# receiver_2v0.net
KiCad netlist of a schematic drawn in EAGLE
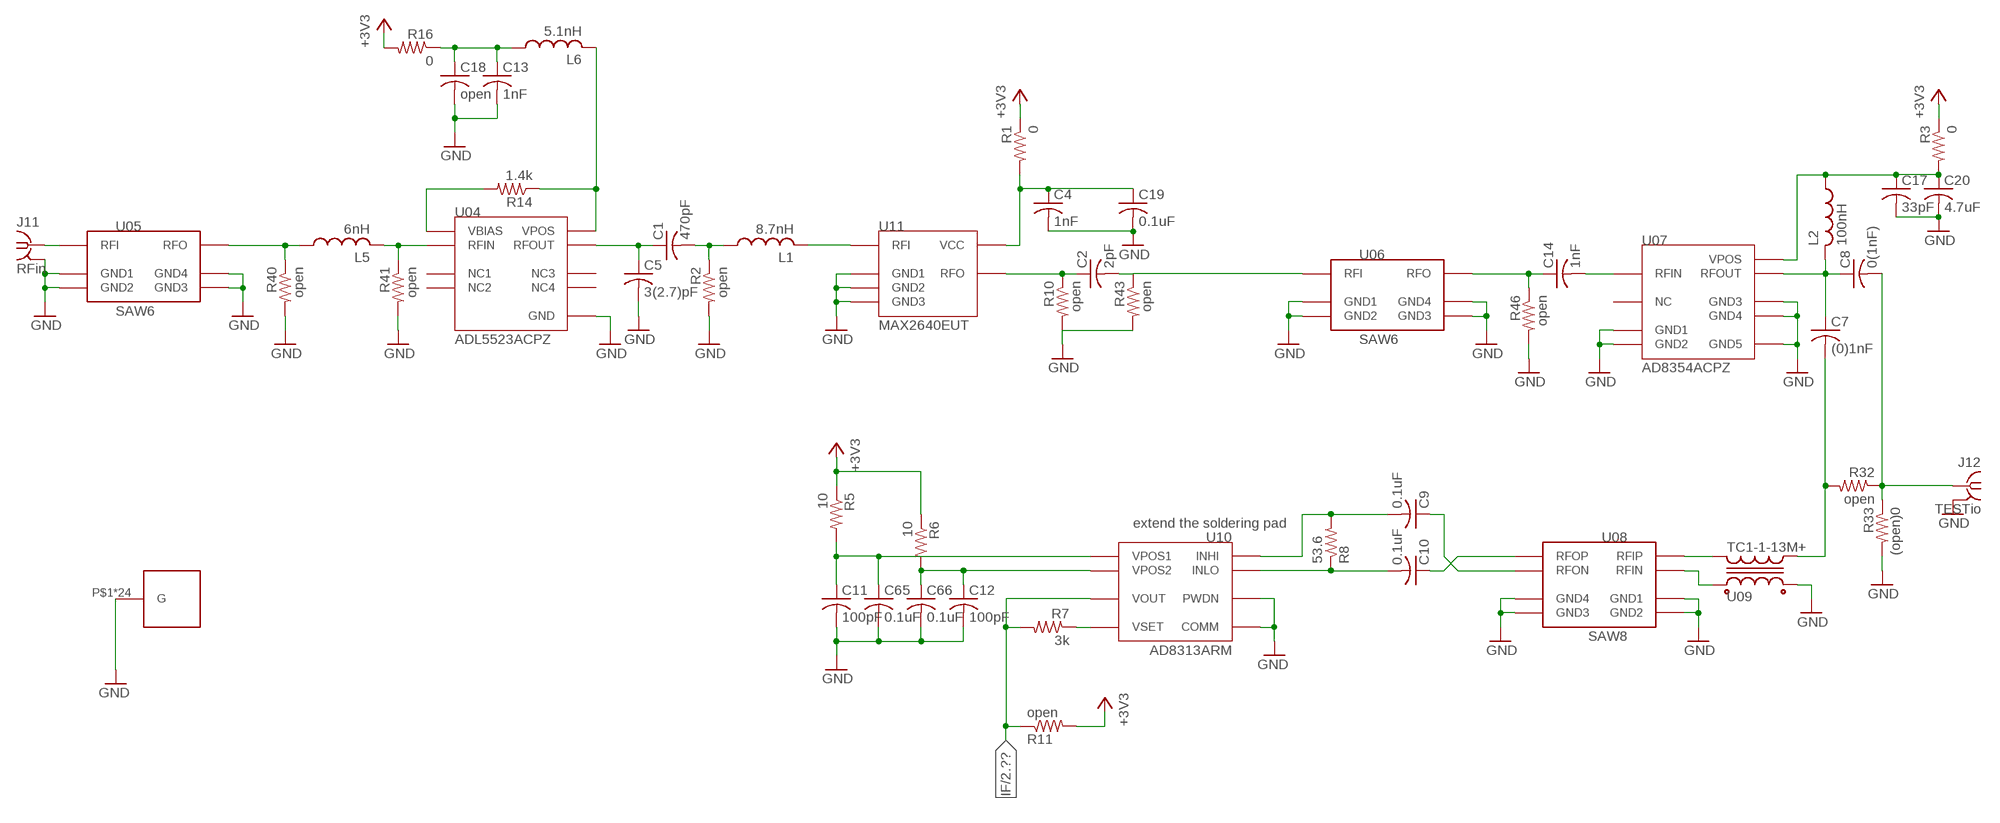
[diagram p0: schematic, sheet 1]
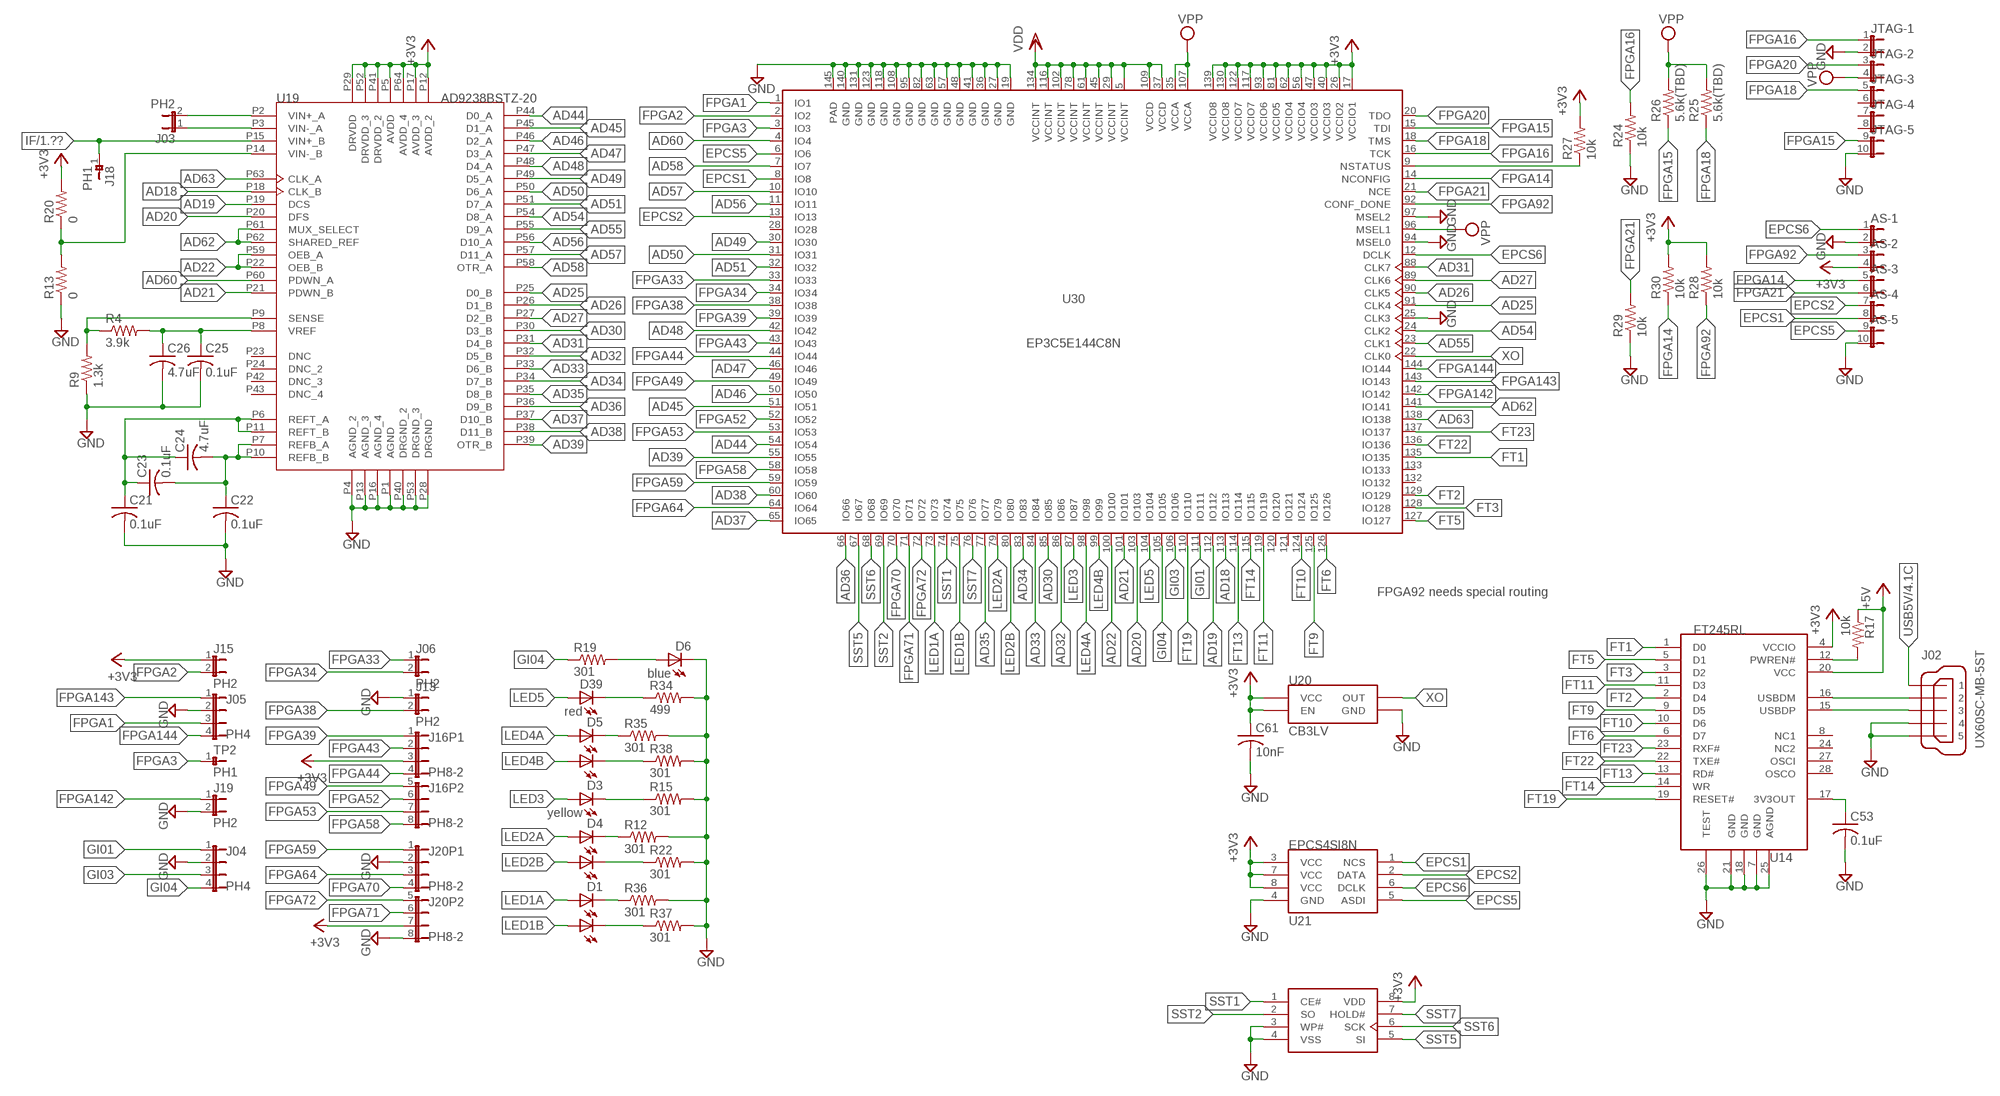
[diagram p1: schematic, sheet 2]
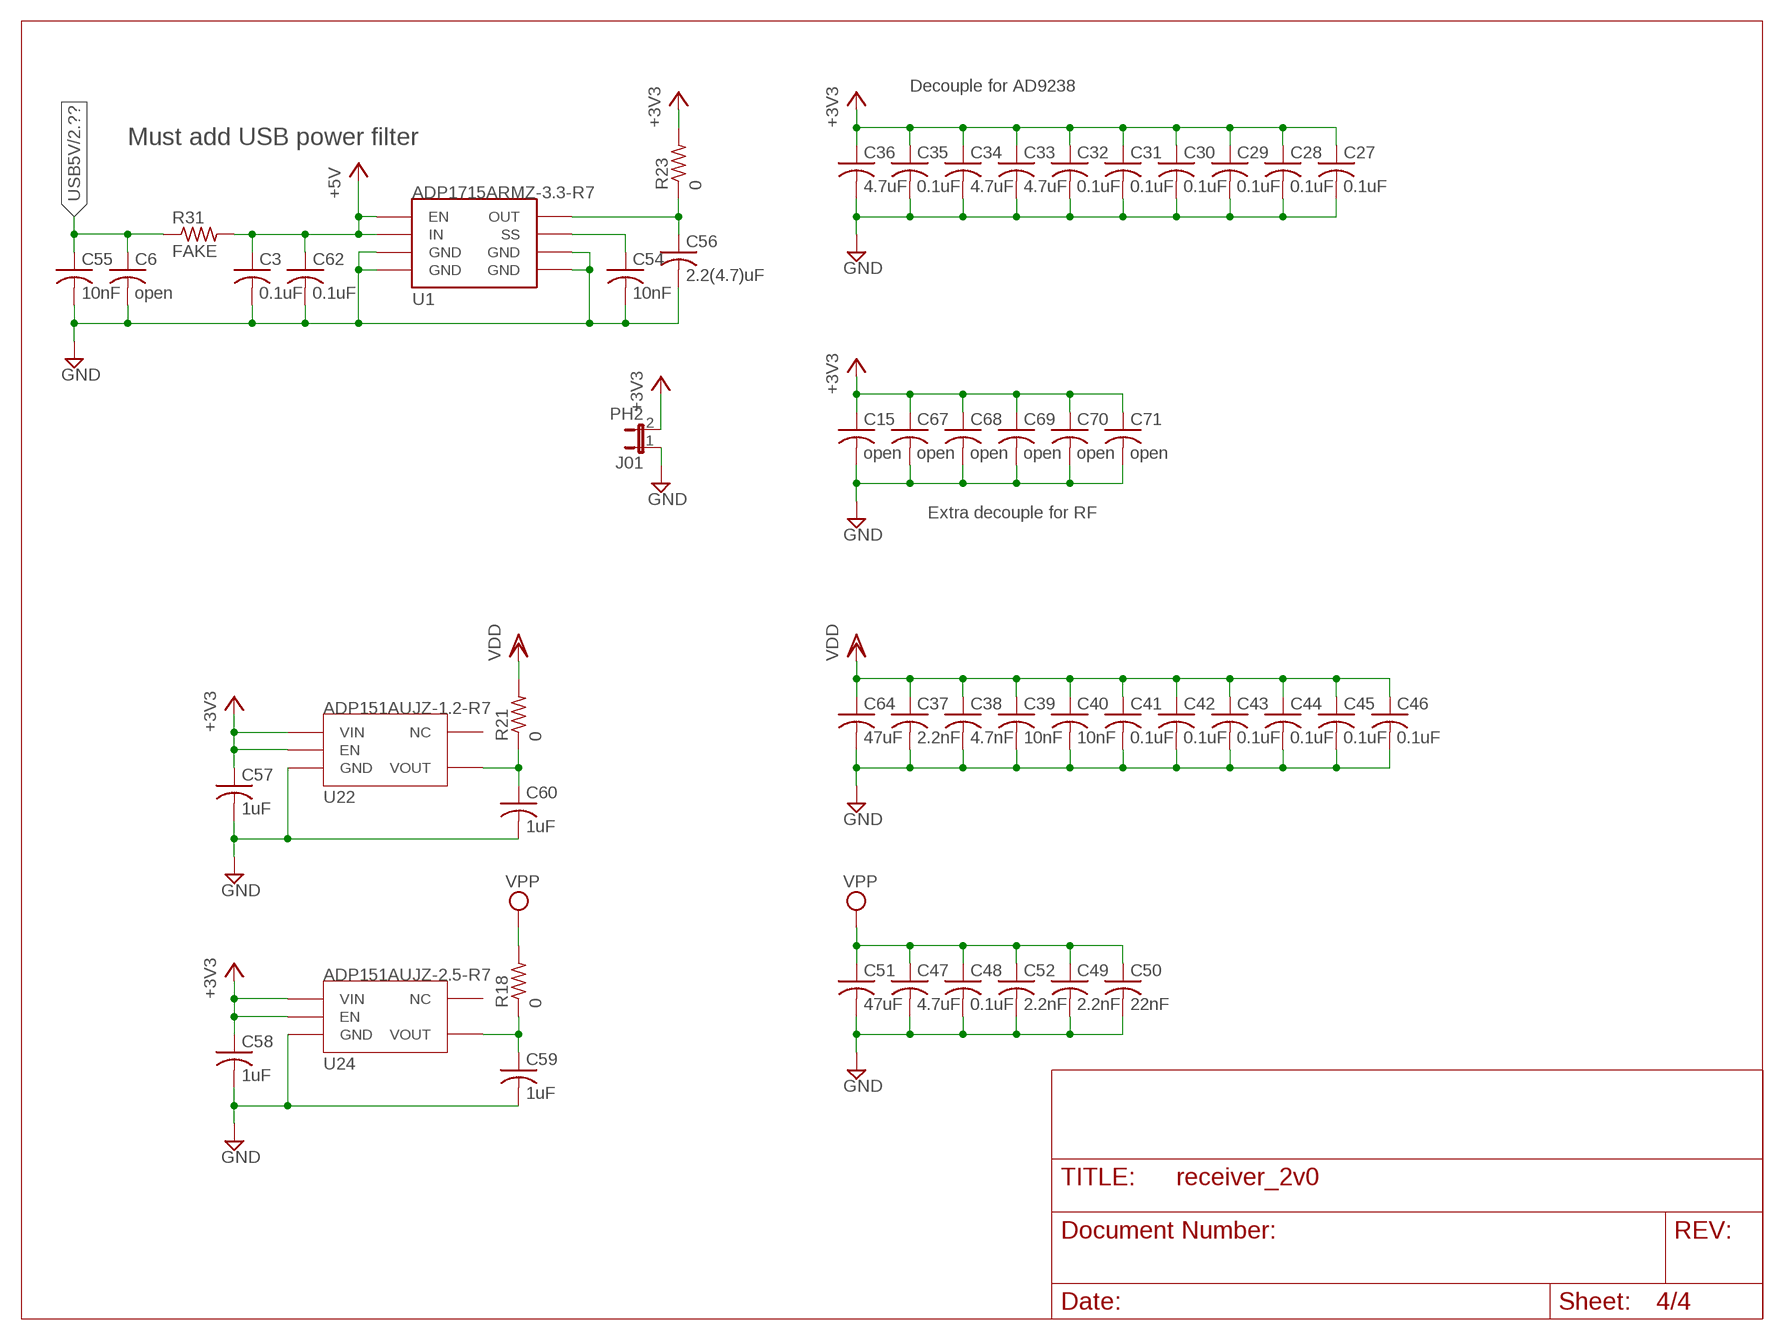
[diagram p2: schematic, sheet 4]

(export (version "E")
  (design (tool "Eeschema 10.0.6"))
  (components
    (comp (ref "C1")
      (value "470pF")
      (footprint "eagle-import:C0603")
      (libsource (lib "eagle-import") (part "C-USC0603"))
    )
    (comp (ref "C2")
      (value "2pF")
      (footprint "eagle-import:C0603")
      (libsource (lib "eagle-import") (part "C-USC0603"))
    )
    (comp (ref "C4")
      (value "1nF")
      (footprint "eagle-import:C0603")
      (libsource (lib "eagle-import") (part "C-USC0603"))
    )
    (comp (ref "C5")
      (value "3(2.7)pF")
      (footprint "eagle-import:C0603")
      (libsource (lib "eagle-import") (part "C-USC0603"))
    )
    (comp (ref "C7")
      (value "(0)1nF")
      (footprint "eagle-import:C0603")
      (libsource (lib "eagle-import") (part "C-USC0603"))
    )
    (comp (ref "C8")
      (value "0(1nF)")
      (footprint "eagle-import:C0603")
      (libsource (lib "eagle-import") (part "C-USC0603"))
    )
    (comp (ref "C9")
      (value "0.1uF")
      (footprint "eagle-import:C0603")
      (libsource (lib "eagle-import") (part "C-USC0603"))
    )
    (comp (ref "C10")
      (value "0.1uF")
      (footprint "eagle-import:C0603")
      (libsource (lib "eagle-import") (part "C-USC0603"))
    )
    (comp (ref "C11")
      (value "100pF")
      (footprint "eagle-import:C0603")
      (libsource (lib "eagle-import") (part "C-USC0603"))
    )
    (comp (ref "C12")
      (value "100pF")
      (footprint "eagle-import:C0603")
      (libsource (lib "eagle-import") (part "C-USC0603"))
    )
    (comp (ref "C13")
      (value "1nF")
      (footprint "eagle-import:C0603")
      (libsource (lib "eagle-import") (part "C-USC0603"))
    )
    (comp (ref "C14")
      (value "1nF")
      (footprint "eagle-import:C0603")
      (libsource (lib "eagle-import") (part "C-USC0603"))
    )
    (comp (ref "C17")
      (value "33pF")
      (footprint "eagle-import:C0603")
      (libsource (lib "eagle-import") (part "C-USC0603"))
    )
    (comp (ref "C18")
      (value "open")
      (footprint "eagle-import:C0603")
      (libsource (lib "eagle-import") (part "C-USC0603"))
    )
    (comp (ref "C19")
      (value "0.1uF")
      (footprint "eagle-import:C0603")
      (libsource (lib "eagle-import") (part "C-USC0603"))
    )
    (comp (ref "C20")
      (value "4.7uF")
      (footprint "eagle-import:C0603")
      (libsource (lib "eagle-import") (part "C-USC0603"))
    )
    (comp (ref "C65")
      (value "0.1uF")
      (footprint "eagle-import:C0603")
      (libsource (lib "eagle-import") (part "C-USC0603"))
    )
    (comp (ref "C66")
      (value "0.1uF")
      (footprint "eagle-import:C0603")
      (libsource (lib "eagle-import") (part "C-USC0603"))
    )
    (comp (ref "J11")
      (value "RFin")
      (footprint "eagle-import:J502-ND-142-0711-821_826")
      (fields
        (field (name "MF") "JOHNSON COMPONENTS")
        (field (name "MPN") "142-0711-821")
        (field (name "MPN_1") "142-0711-821")
        (field (name "OC_FARNELL") "1019328")
        (field (name "OC_NEWARK") "16F3627")
      )
      (libsource (lib "eagle-import") (part "SMA-142-0711-821/826"))
    )
    (comp (ref "J12")
      (value "TESTio")
      (footprint "eagle-import:J502-ND-142-0711-821_826")
      (fields
        (field (name "MF") "JOHNSON COMPONENTS")
        (field (name "MPN") "142-0711-821")
        (field (name "MPN_1") "142-0711-821")
        (field (name "OC_FARNELL") "1019328")
        (field (name "OC_NEWARK") "16F3627")
      )
      (libsource (lib "eagle-import") (part "SMA-142-0711-821/826"))
    )
    (comp (ref "L1")
      (value "8.7nH")
      (footprint "eagle-import:L0603")
      (libsource (lib "eagle-import") (part "L-USL0603"))
    )
    (comp (ref "L2")
      (value "100nH")
      (footprint "eagle-import:L0603")
      (libsource (lib "eagle-import") (part "L-USL0603"))
    )
    (comp (ref "L5")
      (value "6nH")
      (footprint "eagle-import:L0603")
      (libsource (lib "eagle-import") (part "L-USL0603"))
    )
    (comp (ref "L6")
      (value "5.1nH")
      (footprint "eagle-import:L0603")
      (libsource (lib "eagle-import") (part "L-USL0603"))
    )
    (comp (ref "R1")
      (value "0")
      (footprint "eagle-import:R0603")
      (libsource (lib "eagle-import") (part "R-US_R0603"))
    )
    (comp (ref "R2")
      (value "open")
      (footprint "eagle-import:R0603")
      (libsource (lib "eagle-import") (part "R-US_R0603"))
    )
    (comp (ref "R3")
      (value "0")
      (footprint "eagle-import:R0603")
      (libsource (lib "eagle-import") (part "R-US_R0603"))
    )
    (comp (ref "R5")
      (value "10")
      (footprint "eagle-import:R0603")
      (libsource (lib "eagle-import") (part "R-US_R0603"))
    )
    (comp (ref "R6")
      (value "10")
      (footprint "eagle-import:R0603")
      (libsource (lib "eagle-import") (part "R-US_R0603"))
    )
    (comp (ref "R7")
      (value "3k")
      (footprint "eagle-import:R0603")
      (libsource (lib "eagle-import") (part "R-US_R0603"))
    )
    (comp (ref "R8")
      (value "53.6")
      (footprint "eagle-import:R0603")
      (libsource (lib "eagle-import") (part "R-US_R0603"))
    )
    (comp (ref "R10")
      (value "open")
      (footprint "eagle-import:R0603")
      (libsource (lib "eagle-import") (part "R-US_R0603"))
    )
    (comp (ref "R11")
      (value "open")
      (footprint "eagle-import:R0603")
      (libsource (lib "eagle-import") (part "R-US_R0603"))
    )
    (comp (ref "R14")
      (value "1.4k")
      (footprint "eagle-import:R0603")
      (libsource (lib "eagle-import") (part "R-US_R0603"))
    )
    (comp (ref "R16")
      (value "0")
      (footprint "eagle-import:R0603")
      (libsource (lib "eagle-import") (part "R-US_R0603"))
    )
    (comp (ref "R32")
      (value "open")
      (footprint "eagle-import:R0603")
      (libsource (lib "eagle-import") (part "R-US_R0603"))
    )
    (comp (ref "R33")
      (value "(open)0")
      (footprint "eagle-import:R0603")
      (libsource (lib "eagle-import") (part "R-US_R0603"))
    )
    (comp (ref "R40")
      (value "open")
      (footprint "eagle-import:R0603")
      (libsource (lib "eagle-import") (part "R-US_R0603"))
    )
    (comp (ref "R41")
      (value "open")
      (footprint "eagle-import:R0603")
      (libsource (lib "eagle-import") (part "R-US_R0603"))
    )
    (comp (ref "R43")
      (value "open")
      (footprint "eagle-import:R0603")
      (libsource (lib "eagle-import") (part "R-US_R0603"))
    )
    (comp (ref "R46")
      (value "open")
      (footprint "eagle-import:R0603")
      (libsource (lib "eagle-import") (part "R-US_R0603"))
    )
    (comp (ref "U$8")
      (value "BMI-S-5")
      (footprint "eagle-import:BMI-S-105")
      (libsource (lib "eagle-import") (part "BMI-S-5"))
    )
    (comp (ref "U04")
      (value "ADL5523ACPZ")
      (footprint "eagle-import:CP-8-2")
      (libsource (lib "eagle-import") (part "ADL5523ACPZ"))
    )
    (comp (ref "U05")
      (value "SAW6")
      (footprint "eagle-import:SAW6")
      (libsource (lib "eagle-import") (part "SAW6"))
    )
    (comp (ref "U06")
      (value "SAW6")
      (footprint "eagle-import:SAW6")
      (libsource (lib "eagle-import") (part "SAW6"))
    )
    (comp (ref "U07")
      (value "AD8354ACPZ")
      (footprint "eagle-import:CP-8-1")
      (libsource (lib "eagle-import") (part "AD8354ACPZ"))
    )
    (comp (ref "U08")
      (value "SAW8")
      (footprint "eagle-import:SAW8")
      (libsource (lib "eagle-import") (part "SAW8"))
    )
    (comp (ref "U09")
      (value "TC1-1-13M+")
      (footprint "eagle-import:AT224-1A")
      (libsource (lib "eagle-import") (part "TC1-1-13M+"))
    )
    (comp (ref "U10")
      (value "AD8313ARM")
      (footprint "eagle-import:RM-08")
      (libsource (lib "eagle-import") (part "AD8313ARM"))
    )
    (comp (ref "U11")
      (value "MAX2640EUT")
      (footprint "eagle-import:SOT23-6")
      (libsource (lib "eagle-import") (part "MAX2640EUT"))
    )
    (comp (ref "C3")
      (value "0.1uF")
      (footprint "eagle-import:C0603")
      (libsource (lib "eagle-import") (part "C-USC0603"))
    )
    (comp (ref "C6")
      (value "open")
      (footprint "eagle-import:C0603")
      (libsource (lib "eagle-import") (part "C-USC0603"))
    )
    (comp (ref "C15")
      (value "open")
      (footprint "eagle-import:C0603")
      (libsource (lib "eagle-import") (part "C-USC0603"))
    )
    (comp (ref "C27")
      (value "0.1uF")
      (footprint "eagle-import:C0603")
      (libsource (lib "eagle-import") (part "C-USC0603"))
    )
    (comp (ref "C28")
      (value "0.1uF")
      (footprint "eagle-import:C0603")
      (libsource (lib "eagle-import") (part "C-USC0603"))
    )
    (comp (ref "C29")
      (value "0.1uF")
      (footprint "eagle-import:C0603")
      (libsource (lib "eagle-import") (part "C-USC0603"))
    )
    (comp (ref "C30")
      (value "0.1uF")
      (footprint "eagle-import:C0603")
      (libsource (lib "eagle-import") (part "C-USC0603"))
    )
    (comp (ref "C31")
      (value "0.1uF")
      (footprint "eagle-import:C0603")
      (libsource (lib "eagle-import") (part "C-USC0603"))
    )
    (comp (ref "C32")
      (value "0.1uF")
      (footprint "eagle-import:C0603")
      (libsource (lib "eagle-import") (part "C-USC0603"))
    )
    (comp (ref "C33")
      (value "4.7uF")
      (footprint "eagle-import:C0603")
      (libsource (lib "eagle-import") (part "C-USC0603"))
    )
    (comp (ref "C34")
      (value "4.7uF")
      (footprint "eagle-import:C0603")
      (libsource (lib "eagle-import") (part "C-USC0603"))
    )
    (comp (ref "C35")
      (value "0.1uF")
      (footprint "eagle-import:C0603")
      (libsource (lib "eagle-import") (part "C-USC0603"))
    )
    (comp (ref "C36")
      (value "4.7uF")
      (footprint "eagle-import:C0603")
      (libsource (lib "eagle-import") (part "C-USC0603"))
    )
    (comp (ref "C37")
      (value "2.2nF")
      (footprint "eagle-import:C0603")
      (libsource (lib "eagle-import") (part "C-USC0603"))
    )
    (comp (ref "C38")
      (value "4.7nF")
      (footprint "eagle-import:C0603")
      (libsource (lib "eagle-import") (part "C-USC0603"))
    )
    (comp (ref "C39")
      (value "10nF")
      (footprint "eagle-import:C0603")
      (libsource (lib "eagle-import") (part "C-USC0603"))
    )
    (comp (ref "C40")
      (value "10nF")
      (footprint "eagle-import:C0603")
      (libsource (lib "eagle-import") (part "C-USC0603"))
    )
    (comp (ref "C41")
      (value "0.1uF")
      (footprint "eagle-import:C0603")
      (libsource (lib "eagle-import") (part "C-USC0603"))
    )
    (comp (ref "C42")
      (value "0.1uF")
      (footprint "eagle-import:C0603")
      (libsource (lib "eagle-import") (part "C-USC0603"))
    )
    (comp (ref "C43")
      (value "0.1uF")
      (footprint "eagle-import:C0603")
      (libsource (lib "eagle-import") (part "C-USC0603"))
    )
    (comp (ref "C44")
      (value "0.1uF")
      (footprint "eagle-import:C0603")
      (libsource (lib "eagle-import") (part "C-USC0603"))
    )
    (comp (ref "C45")
      (value "0.1uF")
      (footprint "eagle-import:C0603")
      (libsource (lib "eagle-import") (part "C-USC0603"))
    )
    (comp (ref "C46")
      (value "0.1uF")
      (footprint "eagle-import:C0603")
      (libsource (lib "eagle-import") (part "C-USC0603"))
    )
    (comp (ref "C47")
      (value "4.7uF")
      (footprint "eagle-import:C0603")
      (libsource (lib "eagle-import") (part "C-USC0603"))
    )
    (comp (ref "C48")
      (value "0.1uF")
      (footprint "eagle-import:C0603")
      (libsource (lib "eagle-import") (part "C-USC0603"))
    )
    (comp (ref "C49")
      (value "2.2nF")
      (footprint "eagle-import:C0603")
      (libsource (lib "eagle-import") (part "C-USC0603"))
    )
    (comp (ref "C50")
      (value "22nF")
      (footprint "eagle-import:C0603")
      (libsource (lib "eagle-import") (part "C-USC0603"))
    )
    (comp (ref "C51")
      (value "47uF")
      (footprint "eagle-import:C1206")
      (libsource (lib "eagle-import") (part "C-USC1206"))
    )
    (comp (ref "C52")
      (value "2.2nF")
      (footprint "eagle-import:C0603")
      (libsource (lib "eagle-import") (part "C-USC0603"))
    )
    (comp (ref "C54")
      (value "10nF")
      (footprint "eagle-import:C0603")
      (libsource (lib "eagle-import") (part "C-USC0603"))
    )
    (comp (ref "C55")
      (value "10nF")
      (footprint "eagle-import:C0603")
      (libsource (lib "eagle-import") (part "C-USC0603"))
    )
    (comp (ref "C56")
      (value "2.2(4.7)uF")
      (footprint "eagle-import:C0603")
      (libsource (lib "eagle-import") (part "C-USC0603"))
    )
    (comp (ref "C57")
      (value "1uF")
      (footprint "eagle-import:C0603")
      (libsource (lib "eagle-import") (part "C-USC0603"))
    )
    (comp (ref "C58")
      (value "1uF")
      (footprint "eagle-import:C0603")
      (libsource (lib "eagle-import") (part "C-USC0603"))
    )
    (comp (ref "C59")
      (value "1uF")
      (footprint "eagle-import:C0603")
      (libsource (lib "eagle-import") (part "C-USC0603"))
    )
    (comp (ref "C60")
      (value "1uF")
      (footprint "eagle-import:C0603")
      (libsource (lib "eagle-import") (part "C-USC0603"))
    )
    (comp (ref "C62")
      (value "0.1uF")
      (footprint "eagle-import:C0603")
      (libsource (lib "eagle-import") (part "C-USC0603"))
    )
    (comp (ref "C64")
      (value "47uF")
      (footprint "eagle-import:C1206")
      (libsource (lib "eagle-import") (part "C-USC1206"))
    )
    (comp (ref "C67")
      (value "open")
      (footprint "eagle-import:C0603")
      (libsource (lib "eagle-import") (part "C-USC0603"))
    )
    (comp (ref "C68")
      (value "open")
      (footprint "eagle-import:C0603")
      (libsource (lib "eagle-import") (part "C-USC0603"))
    )
    (comp (ref "C69")
      (value "open")
      (footprint "eagle-import:C0603")
      (libsource (lib "eagle-import") (part "C-USC0603"))
    )
    (comp (ref "C70")
      (value "open")
      (footprint "eagle-import:C0603")
      (libsource (lib "eagle-import") (part "C-USC0603"))
    )
    (comp (ref "C71")
      (value "open")
      (footprint "eagle-import:C0603")
      (libsource (lib "eagle-import") (part "C-USC0603"))
    )
    (comp (ref "J01")
      (value "PH2")
      (footprint "eagle-import:PH2")
      (libsource (lib "eagle-import") (part "PH2"))
    )
    (comp (ref "R18")
      (value "0")
      (footprint "eagle-import:R0603")
      (libsource (lib "eagle-import") (part "R-US_R0603"))
    )
    (comp (ref "R21")
      (value "0")
      (footprint "eagle-import:R0603")
      (libsource (lib "eagle-import") (part "R-US_R0603"))
    )
    (comp (ref "R23")
      (value "0")
      (footprint "eagle-import:R0603")
      (libsource (lib "eagle-import") (part "R-US_R0603"))
    )
    (comp (ref "R31")
      (value "FAKE")
      (footprint "eagle-import:R0603")
      (libsource (lib "eagle-import") (part "R-US_R0603"))
    )
    (comp (ref "U1")
      (value "ADP1715ARMZ-3.3-R7")
      (footprint "eagle-import:RM-08")
      (libsource (lib "eagle-import") (part "ADP1715ARMZ-3.3-R7"))
    )
    (comp (ref "U22")
      (value "ADP151AUJZ-1.2-R7")
      (footprint "eagle-import:UJ-5")
      (libsource (lib "eagle-import") (part "ADP151AUJZ-1.2-R7"))
    )
    (comp (ref "U24")
      (value "ADP151AUJZ-2.5-R7")
      (footprint "eagle-import:UJ-5")
      (libsource (lib "eagle-import") (part "ADP151AUJZ-2.5-R7"))
    )
    (comp (ref "AS")
      (value "JP5QE")
      (footprint "eagle-import:JP5Q")
      (libsource (lib "eagle-import") (part "JP5QE"))
    )
    (comp (ref "C21")
      (value "0.1uF")
      (footprint "eagle-import:C0603")
      (libsource (lib "eagle-import") (part "C-USC0603"))
    )
    (comp (ref "C22")
      (value "0.1uF")
      (footprint "eagle-import:C0603")
      (libsource (lib "eagle-import") (part "C-USC0603"))
    )
    (comp (ref "C23")
      (value "0.1uF")
      (footprint "eagle-import:C0603")
      (libsource (lib "eagle-import") (part "C-USC0603"))
    )
    (comp (ref "C24")
      (value "4.7uF")
      (footprint "eagle-import:C0603")
      (libsource (lib "eagle-import") (part "C-USC0603"))
    )
    (comp (ref "C25")
      (value "0.1uF")
      (footprint "eagle-import:C0603")
      (libsource (lib "eagle-import") (part "C-USC0603"))
    )
    (comp (ref "C26")
      (value "4.7uF")
      (footprint "eagle-import:C0603")
      (libsource (lib "eagle-import") (part "C-USC0603"))
    )
    (comp (ref "C53")
      (value "0.1uF")
      (footprint "eagle-import:C0603")
      (libsource (lib "eagle-import") (part "C-USC0603"))
    )
    (comp (ref "C61")
      (value "10nF")
      (footprint "eagle-import:C0603")
      (libsource (lib "eagle-import") (part "C-USC0603"))
    )
    (comp (ref "D1")
      (value "LED0606")
      (footprint "eagle-import:LED0606")
      (libsource (lib "eagle-import") (part "LED0606"))
    )
    (comp (ref "D3")
      (value "yellow")
      (footprint "eagle-import:LED0603")
      (libsource (lib "eagle-import") (part "LED0603"))
    )
    (comp (ref "D4")
      (value "LED0606")
      (footprint "eagle-import:LED0606")
      (libsource (lib "eagle-import") (part "LED0606"))
    )
    (comp (ref "D5")
      (value "LED0606")
      (footprint "eagle-import:LED0606")
      (libsource (lib "eagle-import") (part "LED0606"))
    )
    (comp (ref "D6")
      (value "blue")
      (footprint "eagle-import:LED0603")
      (libsource (lib "eagle-import") (part "LED0603"))
    )
    (comp (ref "D39")
      (value "red")
      (footprint "eagle-import:LED0603")
      (libsource (lib "eagle-import") (part "LED0603"))
    )
    (comp (ref "J02")
      (value "UX60SC-MB-5ST")
      (footprint "eagle-import:UX60SC-MB-5ST")
      (libsource (lib "eagle-import") (part "UX60SC-MB-5ST"))
    )
    (comp (ref "J03")
      (value "PH2")
      (footprint "eagle-import:PH2")
      (libsource (lib "eagle-import") (part "PH2"))
    )
    (comp (ref "J04")
      (value "PH4")
      (footprint "eagle-import:PH4")
      (libsource (lib "eagle-import") (part "PH4"))
    )
    (comp (ref "J05")
      (value "PH4")
      (footprint "eagle-import:PH4")
      (libsource (lib "eagle-import") (part "PH4"))
    )
    (comp (ref "J06")
      (value "PH2")
      (footprint "eagle-import:PH2")
      (libsource (lib "eagle-import") (part "PH2"))
    )
    (comp (ref "J13")
      (value "PH2")
      (footprint "eagle-import:PH2")
      (libsource (lib "eagle-import") (part "PH2"))
    )
    (comp (ref "J15")
      (value "PH2")
      (footprint "eagle-import:PH2")
      (libsource (lib "eagle-import") (part "PH2"))
    )
    (comp (ref "J16")
      (value "PH8-2")
      (footprint "eagle-import:PH8-2")
      (libsource (lib "eagle-import") (part "PH8-2"))
    )
    (comp (ref "J18")
      (value "PH1")
      (footprint "eagle-import:PH1")
      (libsource (lib "eagle-import") (part "PH1"))
    )
    (comp (ref "J19")
      (value "PH2")
      (footprint "eagle-import:PH2")
      (libsource (lib "eagle-import") (part "PH2"))
    )
    (comp (ref "J20")
      (value "PH8-2")
      (footprint "eagle-import:PH8-2")
      (libsource (lib "eagle-import") (part "PH8-2"))
    )
    (comp (ref "JTAG")
      (value "JP5QE")
      (footprint "eagle-import:JP5Q")
      (libsource (lib "eagle-import") (part "JP5QE"))
    )
    (comp (ref "R4")
      (value "3.9k")
      (footprint "eagle-import:R0603")
      (libsource (lib "eagle-import") (part "R-US_R0603"))
    )
    (comp (ref "R9")
      (value "1.3k")
      (footprint "eagle-import:R0603")
      (libsource (lib "eagle-import") (part "R-US_R0603"))
    )
    (comp (ref "R12")
      (value "301")
      (footprint "eagle-import:R0603")
      (libsource (lib "eagle-import") (part "R-US_R0603"))
    )
    (comp (ref "R13")
      (value "0")
      (footprint "eagle-import:R0603")
      (libsource (lib "eagle-import") (part "R-US_R0603"))
    )
    (comp (ref "R15")
      (value "301")
      (footprint "eagle-import:R0603")
      (libsource (lib "eagle-import") (part "R-US_R0603"))
    )
    (comp (ref "R17")
      (value "10k")
      (footprint "eagle-import:R0603")
      (libsource (lib "eagle-import") (part "R-US_R0603"))
    )
    (comp (ref "R19")
      (value "301")
      (footprint "eagle-import:R0603")
      (libsource (lib "eagle-import") (part "R-US_R0603"))
    )
    (comp (ref "R20")
      (value "0")
      (footprint "eagle-import:R0603")
      (libsource (lib "eagle-import") (part "R-US_R0603"))
    )
    (comp (ref "R22")
      (value "301")
      (footprint "eagle-import:R0603")
      (libsource (lib "eagle-import") (part "R-US_R0603"))
    )
    (comp (ref "R24")
      (value "10k")
      (footprint "eagle-import:R0603")
      (libsource (lib "eagle-import") (part "R-US_R0603"))
    )
    (comp (ref "R25")
      (value "5.6k(TBD)")
      (footprint "eagle-import:R0603")
      (libsource (lib "eagle-import") (part "R-US_R0603"))
    )
    (comp (ref "R26")
      (value "5.6k(TBD)")
      (footprint "eagle-import:R0603")
      (libsource (lib "eagle-import") (part "R-US_R0603"))
    )
    (comp (ref "R27")
      (value "10k")
      (footprint "eagle-import:R0603")
      (libsource (lib "eagle-import") (part "R-US_R0603"))
    )
    (comp (ref "R28")
      (value "10k")
      (footprint "eagle-import:R0603")
      (libsource (lib "eagle-import") (part "R-US_R0603"))
    )
    (comp (ref "R29")
      (value "10k")
      (footprint "eagle-import:R0603")
      (libsource (lib "eagle-import") (part "R-US_R0603"))
    )
    (comp (ref "R30")
      (value "10k")
      (footprint "eagle-import:R0603")
      (libsource (lib "eagle-import") (part "R-US_R0603"))
    )
    (comp (ref "R34")
      (value "499")
      (footprint "eagle-import:R0603")
      (libsource (lib "eagle-import") (part "R-US_R0603"))
    )
    (comp (ref "R35")
      (value "301")
      (footprint "eagle-import:R0603")
      (libsource (lib "eagle-import") (part "R-US_R0603"))
    )
    (comp (ref "R36")
      (value "301")
      (footprint "eagle-import:R0603")
      (libsource (lib "eagle-import") (part "R-US_R0603"))
    )
    (comp (ref "R37")
      (value "301")
      (footprint "eagle-import:R0603")
      (libsource (lib "eagle-import") (part "R-US_R0603"))
    )
    (comp (ref "R38")
      (value "301")
      (footprint "eagle-import:R0603")
      (libsource (lib "eagle-import") (part "R-US_R0603"))
    )
    (comp (ref "TP2")
      (value "PH1")
      (footprint "eagle-import:PH1")
      (libsource (lib "eagle-import") (part "PH1"))
    )
    (comp (ref "U14")
      (value "FT245RL")
      (footprint "eagle-import:SSOP-28")
      (libsource (lib "eagle-import") (part "FT245RL"))
    )
    (comp (ref "U19")
      (value "AD9238BSTZ-20")
      (footprint "eagle-import:ST-64-1")
      (libsource (lib "eagle-import") (part "AD9238BSTZ-20"))
    )
    (comp (ref "U20")
      (value "CB3LV")
      (footprint "eagle-import:CB3")
      (libsource (lib "eagle-import") (part "CB3LV"))
    )
    (comp (ref "U21")
      (value "EPCS4SI8N")
      (footprint "eagle-import:SOIC-8")
      (libsource (lib "eagle-import") (part "EPCS4SI8N"))
    )
    (comp (ref "U23")
      (value "SST25VF512A-33-4C-SAE")
      (footprint "eagle-import:SOIC-8")
      (libsource (lib "eagle-import") (part "SST25VF512A-33-4C-SAE"))
    )
    (comp (ref "U30")
      (value "EP3C5E144C8N")
      (footprint "eagle-import:EQFP144")
      (libsource (lib "eagle-import") (part "EP3C5E144C8N"))
    )
  )
  (nets
    (net (code "1") (name "+3V3") (class "Default")
      (node (ref "AS") (pin "4") (pinfunction "2_4") (pintype "passive"))
      (node (ref "C15") (pin "1") (pinfunction "1_1") (pintype "passive"))
      (node (ref "C27") (pin "1") (pinfunction "1_1") (pintype "passive"))
      (node (ref "C28") (pin "1") (pinfunction "1_1") (pintype "passive"))
      (node (ref "C29") (pin "1") (pinfunction "1_1") (pintype "passive"))
      (node (ref "C30") (pin "1") (pinfunction "1_1") (pintype "passive"))
      (node (ref "C31") (pin "1") (pinfunction "1_1") (pintype "passive"))
      (node (ref "C32") (pin "1") (pinfunction "1_1") (pintype "passive"))
      (node (ref "C33") (pin "1") (pinfunction "1_1") (pintype "passive"))
      (node (ref "C34") (pin "1") (pinfunction "1_1") (pintype "passive"))
      (node (ref "C35") (pin "1") (pinfunction "1_1") (pintype "passive"))
      (node (ref "C36") (pin "1") (pinfunction "1_1") (pintype "passive"))
      (node (ref "C57") (pin "1") (pinfunction "1_1") (pintype "passive"))
      (node (ref "C58") (pin "1") (pinfunction "1_1") (pintype "passive"))
      (node (ref "C61") (pin "1") (pinfunction "1_1") (pintype "passive"))
      (node (ref "C67") (pin "1") (pinfunction "1_1") (pintype "passive"))
      (node (ref "C68") (pin "1") (pinfunction "1_1") (pintype "passive"))
      (node (ref "C69") (pin "1") (pinfunction "1_1") (pintype "passive"))
      (node (ref "C70") (pin "1") (pinfunction "1_1") (pintype "passive"))
      (node (ref "C71") (pin "1") (pinfunction "1_1") (pintype "passive"))
      (node (ref "J01") (pin "2") (pinfunction "2_2") (pintype "passive"))
      (node (ref "J15") (pin "1") (pinfunction "1_1") (pintype "passive"))
      (node (ref "J16") (pin "3") (pinfunction "3_3") (pintype "passive"))
      (node (ref "J20") (pin "7") (pinfunction "3_7") (pintype "passive"))
      (node (ref "R1") (pin "1") (pinfunction "1_1") (pintype "passive"))
      (node (ref "R11") (pin "2") (pinfunction "2_2") (pintype "passive"))
      (node (ref "R16") (pin "2") (pinfunction "2_2") (pintype "passive"))
      (node (ref "R20") (pin "2") (pinfunction "2_2") (pintype "passive"))
      (node (ref "R23") (pin "2") (pinfunction "2_2") (pintype "passive"))
      (node (ref "R27") (pin "2") (pinfunction "2_2") (pintype "passive"))
      (node (ref "R28") (pin "2") (pinfunction "2_2") (pintype "passive"))
      (node (ref "R3") (pin "1") (pinfunction "1_1") (pintype "passive"))
      (node (ref "R30") (pin "2") (pinfunction "2_2") (pintype "passive"))
      (node (ref "R5") (pin "1") (pinfunction "1_1") (pintype "passive"))
      (node (ref "R6") (pin "1") (pinfunction "1_1") (pintype "passive"))
      (node (ref "U14") (pin "4") (pinfunction "VCCIO_4") (pintype "bidirectional"))
      (node (ref "U19") (pin "P12") (pinfunction "AVDD_2_P12") (pintype "power_in"))
      (node (ref "U19") (pin "P17") (pinfunction "AVDD_3_P17") (pintype "power_in"))
      (node (ref "U19") (pin "P29") (pinfunction "DRVDD_P29") (pintype "power_in"))
      (node (ref "U19") (pin "P41") (pinfunction "DRVDD_2_P41") (pintype "power_in"))
      (node (ref "U19") (pin "P5") (pinfunction "AVDD_P5") (pintype "power_in"))
      (node (ref "U19") (pin "P52") (pinfunction "DRVDD_3_P52") (pintype "power_in"))
      (node (ref "U19") (pin "P64") (pinfunction "AVDD_4_P64") (pintype "power_in"))
      (node (ref "U20") (pin "1") (pinfunction "EN_1") (pintype "bidirectional"))
      (node (ref "U20") (pin "4") (pinfunction "VCC_4") (pintype "bidirectional"))
      (node (ref "U21") (pin "3") (pinfunction "VCC_3") (pintype "bidirectional"))
      (node (ref "U21") (pin "7") (pinfunction "VCC_7") (pintype "bidirectional"))
      (node (ref "U21") (pin "8") (pinfunction "VCC_8") (pintype "bidirectional"))
      (node (ref "U22") (pin "1") (pinfunction "VIN_1") (pintype "passive"))
      (node (ref "U22") (pin "3") (pinfunction "EN_3") (pintype "passive"))
      (node (ref "U23") (pin "8") (pinfunction "VDD_8") (pintype "bidirectional"))
      (node (ref "U24") (pin "1") (pinfunction "VIN_1") (pintype "passive"))
      (node (ref "U24") (pin "3") (pinfunction "EN_3") (pintype "passive"))
      (node (ref "U30") (pin "117") (pinfunction "VCCIO7_117") (pintype "power_in"))
      (node (ref "U30") (pin "122") (pinfunction "VCCIO7_122") (pintype "power_in"))
      (node (ref "U30") (pin "130") (pinfunction "VCCIO8_130") (pintype "power_in"))
      (node (ref "U30") (pin "139") (pinfunction "VCCIO8_139") (pintype "power_in"))
      (node (ref "U30") (pin "17") (pinfunction "VCCIO1_17") (pintype "power_in"))
      (node (ref "U30") (pin "26") (pinfunction "VCCIO2_26") (pintype "power_in"))
      (node (ref "U30") (pin "40") (pinfunction "VCCIO3_40") (pintype "power_in"))
      (node (ref "U30") (pin "47") (pinfunction "VCCIO3_47") (pintype "power_in"))
      (node (ref "U30") (pin "56") (pinfunction "VCCIO4_56") (pintype "power_in"))
      (node (ref "U30") (pin "62") (pinfunction "VCCIO4_62") (pintype "power_in"))
      (node (ref "U30") (pin "81") (pinfunction "VCCIO5_81") (pintype "power_in"))
      (node (ref "U30") (pin "93") (pinfunction "VCCIO6_93") (pintype "power_in"))
    )
    (net (code "2") (name "+5V") (class "Default")
      (node (ref "C3") (pin "1") (pinfunction "1_1") (pintype "passive"))
      (node (ref "C62") (pin "1") (pinfunction "1_1") (pintype "passive"))
      (node (ref "R17") (pin "1") (pinfunction "1_1") (pintype "passive"))
      (node (ref "R31") (pin "2") (pinfunction "2_2") (pintype "passive"))
      (node (ref "U1") (pin "1") (pinfunction "EN_1") (pintype "passive"))
      (node (ref "U1") (pin "2") (pinfunction "IN_2") (pintype "passive"))
      (node (ref "U14") (pin "20") (pinfunction "VCC_20") (pintype "bidirectional"))
    )
    (net (code "3") (name "AD18") (class "Default")
      (node (ref "U19") (pin "P18") (pinfunction "CLK_B_P18") (pintype "passive"))
      (node (ref "U30") (pin "113") (pinfunction "IO113_113") (pintype "bidirectional"))
    )
    (net (code "4") (name "AD19") (class "Default")
      (node (ref "U19") (pin "P19") (pinfunction "DCS_P19") (pintype "passive"))
      (node (ref "U30") (pin "112") (pinfunction "IO112_112") (pintype "bidirectional"))
    )
    (net (code "5") (name "AD20") (class "Default")
      (node (ref "U19") (pin "P20") (pinfunction "DFS_P20") (pintype "passive"))
      (node (ref "U30") (pin "103") (pinfunction "IO103_103") (pintype "bidirectional"))
    )
    (net (code "6") (name "AD21") (class "Default")
      (node (ref "U19") (pin "P21") (pinfunction "PDWN_B_P21") (pintype "passive"))
      (node (ref "U30") (pin "101") (pinfunction "IO101_101") (pintype "bidirectional"))
    )
    (net (code "7") (name "AD22") (class "Default")
      (node (ref "U19") (pin "P22") (pinfunction "OEB_B_P22") (pintype "passive"))
      (node (ref "U19") (pin "P59") (pinfunction "OEB_A_P59") (pintype "passive"))
      (node (ref "U30") (pin "100") (pinfunction "IO100_100") (pintype "bidirectional"))
    )
    (net (code "8") (name "AD25") (class "Default")
      (node (ref "U19") (pin "P25") (pinfunction "D0_B_P25") (pintype "passive"))
      (node (ref "U30") (pin "91") (pinfunction "CLK4_91") (pintype "passive"))
    )
    (net (code "9") (name "AD26") (class "Default")
      (node (ref "U19") (pin "P26") (pinfunction "D1_B_P26") (pintype "passive"))
      (node (ref "U30") (pin "90") (pinfunction "CLK5_90") (pintype "passive"))
    )
    (net (code "10") (name "AD27") (class "Default")
      (node (ref "U19") (pin "P27") (pinfunction "D2_B_P27") (pintype "passive"))
      (node (ref "U30") (pin "89") (pinfunction "CLK6_89") (pintype "passive"))
    )
    (net (code "11") (name "AD30") (class "Default")
      (node (ref "U19") (pin "P30") (pinfunction "D3_B_P30") (pintype "passive"))
      (node (ref "U30") (pin "85") (pinfunction "IO85_85") (pintype "bidirectional"))
    )
    (net (code "12") (name "AD31") (class "Default")
      (node (ref "U19") (pin "P31") (pinfunction "D4_B_P31") (pintype "passive"))
      (node (ref "U30") (pin "88") (pinfunction "CLK7_88") (pintype "passive"))
    )
    (net (code "13") (name "AD32") (class "Default")
      (node (ref "U19") (pin "P32") (pinfunction "D5_B_P32") (pintype "passive"))
      (node (ref "U30") (pin "86") (pinfunction "IO86_86") (pintype "bidirectional"))
    )
    (net (code "14") (name "AD33") (class "Default")
      (node (ref "U19") (pin "P33") (pinfunction "D6_B_P33") (pintype "passive"))
      (node (ref "U30") (pin "84") (pinfunction "IO84_84") (pintype "bidirectional"))
    )
    (net (code "15") (name "AD34") (class "Default")
      (node (ref "U19") (pin "P34") (pinfunction "D7_B_P34") (pintype "passive"))
      (node (ref "U30") (pin "83") (pinfunction "IO83_83") (pintype "bidirectional"))
    )
    (net (code "16") (name "AD35") (class "Default")
      (node (ref "U19") (pin "P35") (pinfunction "D8_B_P35") (pintype "passive"))
      (node (ref "U30") (pin "77") (pinfunction "IO77_77") (pintype "bidirectional"))
    )
    (net (code "17") (name "AD36") (class "Default")
      (node (ref "U19") (pin "P36") (pinfunction "D9_B_P36") (pintype "passive"))
      (node (ref "U30") (pin "66") (pinfunction "IO66_66") (pintype "bidirectional"))
    )
    (net (code "18") (name "AD37") (class "Default")
      (node (ref "U19") (pin "P37") (pinfunction "D10_B_P37") (pintype "passive"))
      (node (ref "U30") (pin "65") (pinfunction "IO65_65") (pintype "bidirectional"))
    )
    (net (code "19") (name "AD38") (class "Default")
      (node (ref "U19") (pin "P38") (pinfunction "D11_B_P38") (pintype "passive"))
      (node (ref "U30") (pin "60") (pinfunction "IO60_60") (pintype "bidirectional"))
    )
    (net (code "20") (name "AD39") (class "Default")
      (node (ref "U19") (pin "P39") (pinfunction "OTR_B_P39") (pintype "passive"))
      (node (ref "U30") (pin "55") (pinfunction "IO55_55") (pintype "bidirectional"))
    )
    (net (code "21") (name "AD44") (class "Default")
      (node (ref "U19") (pin "P44") (pinfunction "D0_A_P44") (pintype "passive"))
      (node (ref "U30") (pin "54") (pinfunction "IO54_54") (pintype "bidirectional"))
    )
    (net (code "22") (name "AD45") (class "Default")
      (node (ref "U19") (pin "P45") (pinfunction "D1_A_P45") (pintype "passive"))
      (node (ref "U30") (pin "51") (pinfunction "IO51_51") (pintype "bidirectional"))
    )
    (net (code "23") (name "AD46") (class "Default")
      (node (ref "U19") (pin "P46") (pinfunction "D2_A_P46") (pintype "passive"))
      (node (ref "U30") (pin "50") (pinfunction "IO50_50") (pintype "bidirectional"))
    )
    (net (code "24") (name "AD47") (class "Default")
      (node (ref "U19") (pin "P47") (pinfunction "D3_A_P47") (pintype "passive"))
      (node (ref "U30") (pin "46") (pinfunction "IO46_46") (pintype "bidirectional"))
    )
    (net (code "25") (name "AD48") (class "Default")
      (node (ref "U19") (pin "P48") (pinfunction "D4_A_P48") (pintype "passive"))
      (node (ref "U30") (pin "42") (pinfunction "IO42_42") (pintype "bidirectional"))
    )
    (net (code "26") (name "AD49") (class "Default")
      (node (ref "U19") (pin "P49") (pinfunction "D5_A_P49") (pintype "passive"))
      (node (ref "U30") (pin "30") (pinfunction "IO30_30") (pintype "bidirectional"))
    )
    (net (code "27") (name "AD50") (class "Default")
      (node (ref "U19") (pin "P50") (pinfunction "D6_A_P50") (pintype "passive"))
      (node (ref "U30") (pin "31") (pinfunction "IO31_31") (pintype "bidirectional"))
    )
    (net (code "28") (name "AD51") (class "Default")
      (node (ref "U19") (pin "P51") (pinfunction "D7_A_P51") (pintype "passive"))
      (node (ref "U30") (pin "32") (pinfunction "IO32_32") (pintype "bidirectional"))
    )
    (net (code "29") (name "AD54") (class "Default")
      (node (ref "U19") (pin "P54") (pinfunction "D8_A_P54") (pintype "passive"))
      (node (ref "U30") (pin "24") (pinfunction "CLK2_24") (pintype "passive"))
    )
    (net (code "30") (name "AD55") (class "Default")
      (node (ref "U19") (pin "P55") (pinfunction "D9_A_P55") (pintype "passive"))
      (node (ref "U30") (pin "23") (pinfunction "CLK1_23") (pintype "passive"))
    )
    (net (code "31") (name "AD56") (class "Default")
      (node (ref "U19") (pin "P56") (pinfunction "D10_A_P56") (pintype "passive"))
      (node (ref "U30") (pin "11") (pinfunction "IO11_11") (pintype "bidirectional"))
    )
    (net (code "32") (name "AD57") (class "Default")
      (node (ref "U19") (pin "P57") (pinfunction "D11_A_P57") (pintype "passive"))
      (node (ref "U30") (pin "10") (pinfunction "IO10_10") (pintype "bidirectional"))
    )
    (net (code "33") (name "AD58") (class "Default")
      (node (ref "U19") (pin "P58") (pinfunction "OTR_A_P58") (pintype "passive"))
      (node (ref "U30") (pin "7") (pinfunction "IO7_7") (pintype "output"))
    )
    (net (code "34") (name "AD60") (class "Default")
      (node (ref "U19") (pin "P60") (pinfunction "PDWN_A_P60") (pintype "passive"))
      (node (ref "U30") (pin "4") (pinfunction "IO4_4") (pintype "passive"))
    )
    (net (code "35") (name "AD62") (class "Default")
      (node (ref "U19") (pin "P61") (pinfunction "MUX_SELECT_P61") (pintype "passive"))
      (node (ref "U19") (pin "P62") (pinfunction "SHARED_REF_P62") (pintype "passive"))
      (node (ref "U30") (pin "141") (pinfunction "IO141_141") (pintype "bidirectional"))
    )
    (net (code "36") (name "AD63") (class "Default")
      (node (ref "U19") (pin "P63") (pinfunction "CLK_A_P63") (pintype "passive"))
      (node (ref "U30") (pin "138") (pinfunction "IO138_138") (pintype "bidirectional"))
    )
    (net (code "37") (name "EPCS1") (class "Default")
      (node (ref "AS") (pin "8") (pinfunction "2_8") (pintype "passive"))
      (node (ref "U21") (pin "1") (pinfunction "NCS_1") (pintype "bidirectional"))
      (node (ref "U30") (pin "8") (pinfunction "IO8_8") (pintype "output"))
    )
    (net (code "38") (name "EPCS2") (class "Default")
      (node (ref "AS") (pin "7") (pinfunction "1_7") (pintype "passive"))
      (node (ref "U21") (pin "2") (pinfunction "DATA_2") (pintype "bidirectional"))
      (node (ref "U30") (pin "13") (pinfunction "IO13_13") (pintype "bidirectional"))
    )
    (net (code "39") (name "EPCS5") (class "Default")
      (node (ref "AS") (pin "9") (pinfunction "1_9") (pintype "passive"))
      (node (ref "U21") (pin "5") (pinfunction "ASDI_5") (pintype "bidirectional"))
      (node (ref "U30") (pin "6") (pinfunction "IO6_6") (pintype "passive"))
    )
    (net (code "40") (name "EPCS6") (class "Default")
      (node (ref "AS") (pin "1") (pinfunction "1_1") (pintype "passive"))
      (node (ref "U21") (pin "6") (pinfunction "DCLK_6") (pintype "bidirectional"))
      (node (ref "U30") (pin "12") (pinfunction "DCLK_12") (pintype "passive"))
    )
    (net (code "41") (name "FPGA1") (class "Default")
      (node (ref "J05") (pin "3") (pinfunction "3_3") (pintype "passive"))
      (node (ref "U30") (pin "1") (pinfunction "IO1_1") (pintype "passive"))
    )
    (net (code "42") (name "FPGA2") (class "Default")
      (node (ref "J15") (pin "2") (pinfunction "2_2") (pintype "passive"))
      (node (ref "U30") (pin "2") (pinfunction "IO2_2") (pintype "passive"))
    )
    (net (code "43") (name "FPGA3") (class "Default")
      (node (ref "TP2") (pin "1") (pinfunction "1_1") (pintype "passive"))
      (node (ref "U30") (pin "3") (pinfunction "IO3_3") (pintype "passive"))
    )
    (net (code "44") (name "FPGA14") (class "Default")
      (node (ref "AS") (pin "5") (pinfunction "1_5") (pintype "passive"))
      (node (ref "R30") (pin "1") (pinfunction "1_1") (pintype "passive"))
      (node (ref "U30") (pin "14") (pinfunction "NCONFIG_14") (pintype "input"))
    )
    (net (code "45") (name "FPGA15") (class "Default")
      (node (ref "JTAG") (pin "9") (pinfunction "1_9") (pintype "passive"))
      (node (ref "R26") (pin "1") (pinfunction "1_1") (pintype "passive"))
      (node (ref "U30") (pin "15") (pinfunction "TDI_15") (pintype "input"))
    )
    (net (code "46") (name "FPGA16") (class "Default")
      (node (ref "JTAG") (pin "1") (pinfunction "1_1") (pintype "passive"))
      (node (ref "R24") (pin "2") (pinfunction "2_2") (pintype "passive"))
      (node (ref "U30") (pin "16") (pinfunction "TCK_16") (pintype "input"))
    )
    (net (code "47") (name "FPGA18") (class "Default")
      (node (ref "JTAG") (pin "5") (pinfunction "1_5") (pintype "passive"))
      (node (ref "R25") (pin "1") (pinfunction "1_1") (pintype "passive"))
      (node (ref "U30") (pin "18") (pinfunction "TMS_18") (pintype "input"))
    )
    (net (code "48") (name "FPGA20") (class "Default")
      (node (ref "JTAG") (pin "3") (pinfunction "1_3") (pintype "passive"))
      (node (ref "U30") (pin "20") (pinfunction "TDO_20") (pintype "output"))
    )
    (net (code "49") (name "FPGA21") (class "Default")
      (node (ref "AS") (pin "6") (pinfunction "2_6") (pintype "passive"))
      (node (ref "R29") (pin "2") (pinfunction "2_2") (pintype "passive"))
      (node (ref "U30") (pin "21") (pinfunction "NCE_21") (pintype "input"))
    )
    (net (code "50") (name "FPGA33") (class "Default")
      (node (ref "J06") (pin "1") (pinfunction "1_1") (pintype "passive"))
      (node (ref "U30") (pin "33") (pinfunction "IO33_33") (pintype "bidirectional"))
    )
    (net (code "51") (name "FPGA34") (class "Default")
      (node (ref "J06") (pin "2") (pinfunction "2_2") (pintype "passive"))
      (node (ref "U30") (pin "34") (pinfunction "IO34_34") (pintype "bidirectional"))
    )
    (net (code "52") (name "FPGA38") (class "Default")
      (node (ref "J13") (pin "2") (pinfunction "2_2") (pintype "passive"))
      (node (ref "U30") (pin "38") (pinfunction "IO38_38") (pintype "bidirectional"))
    )
    (net (code "53") (name "FPGA39") (class "Default")
      (node (ref "J16") (pin "1") (pinfunction "1_1") (pintype "passive"))
      (node (ref "U30") (pin "39") (pinfunction "IO39_39") (pintype "bidirectional"))
    )
    (net (code "54") (name "FPGA43") (class "Default")
      (node (ref "J16") (pin "2") (pinfunction "2_2") (pintype "passive"))
      (node (ref "U30") (pin "43") (pinfunction "IO43_43") (pintype "bidirectional"))
    )
    (net (code "55") (name "FPGA44") (class "Default")
      (node (ref "J16") (pin "4") (pinfunction "4_4") (pintype "passive"))
      (node (ref "U30") (pin "44") (pinfunction "IO44_44") (pintype "bidirectional"))
    )
    (net (code "56") (name "FPGA49") (class "Default")
      (node (ref "J16") (pin "5") (pinfunction "1_5") (pintype "passive"))
      (node (ref "U30") (pin "49") (pinfunction "IO49_49") (pintype "bidirectional"))
    )
    (net (code "57") (name "FPGA52") (class "Default")
      (node (ref "J16") (pin "6") (pinfunction "2_6") (pintype "passive"))
      (node (ref "U30") (pin "52") (pinfunction "IO52_52") (pintype "bidirectional"))
    )
    (net (code "58") (name "FPGA53") (class "Default")
      (node (ref "J16") (pin "7") (pinfunction "3_7") (pintype "passive"))
      (node (ref "U30") (pin "53") (pinfunction "IO53_53") (pintype "bidirectional"))
    )
    (net (code "59") (name "FPGA58") (class "Default")
      (node (ref "J16") (pin "8") (pinfunction "4_8") (pintype "passive"))
      (node (ref "U30") (pin "58") (pinfunction "IO58_58") (pintype "bidirectional"))
    )
    (net (code "60") (name "FPGA59") (class "Default")
      (node (ref "J20") (pin "1") (pinfunction "1_1") (pintype "passive"))
      (node (ref "U30") (pin "59") (pinfunction "IO59_59") (pintype "bidirectional"))
    )
    (net (code "61") (name "FPGA64") (class "Default")
      (node (ref "J20") (pin "3") (pinfunction "3_3") (pintype "passive"))
      (node (ref "U30") (pin "64") (pinfunction "IO64_64") (pintype "bidirectional"))
    )
    (net (code "62") (name "FPGA70") (class "Default")
      (node (ref "J20") (pin "4") (pinfunction "4_4") (pintype "passive"))
      (node (ref "U30") (pin "70") (pinfunction "IO70_70") (pintype "bidirectional"))
    )
    (net (code "63") (name "FPGA71") (class "Default")
      (node (ref "J20") (pin "6") (pinfunction "2_6") (pintype "passive"))
      (node (ref "U30") (pin "71") (pinfunction "IO71_71") (pintype "bidirectional"))
    )
    (net (code "64") (name "FPGA72") (class "Default")
      (node (ref "J20") (pin "5") (pinfunction "1_5") (pintype "passive"))
      (node (ref "U30") (pin "72") (pinfunction "IO72_72") (pintype "bidirectional"))
    )
    (net (code "65") (name "FPGA92") (class "Default")
      (node (ref "AS") (pin "3") (pinfunction "1_3") (pintype "passive"))
      (node (ref "R28") (pin "1") (pinfunction "1_1") (pintype "passive"))
      (node (ref "U30") (pin "92") (pinfunction "CONF_DONE_92") (pintype "input"))
    )
    (net (code "66") (name "FPGA142") (class "Default")
      (node (ref "J19") (pin "1") (pinfunction "1_1") (pintype "passive"))
      (node (ref "U30") (pin "142") (pinfunction "IO142_142") (pintype "bidirectional"))
    )
    (net (code "67") (name "FPGA143") (class "Default")
      (node (ref "J05") (pin "1") (pinfunction "1_1") (pintype "passive"))
      (node (ref "U30") (pin "143") (pinfunction "IO143_143") (pintype "bidirectional"))
    )
    (net (code "68") (name "FPGA144") (class "Default")
      (node (ref "J05") (pin "4") (pinfunction "4_4") (pintype "passive"))
      (node (ref "U30") (pin "144") (pinfunction "IO144_144") (pintype "bidirectional"))
    )
    (net (code "69") (name "FT1") (class "Default")
      (node (ref "U14") (pin "1") (pinfunction "D0_1") (pintype "bidirectional"))
      (node (ref "U30") (pin "135") (pinfunction "IO135_135") (pintype "bidirectional"))
    )
    (net (code "70") (name "FT2") (class "Default")
      (node (ref "U14") (pin "2") (pinfunction "D4_2") (pintype "bidirectional"))
      (node (ref "U30") (pin "129") (pinfunction "IO129_129") (pintype "bidirectional"))
    )
    (net (code "71") (name "FT3") (class "Default")
      (node (ref "U14") (pin "3") (pinfunction "D2_3") (pintype "bidirectional"))
      (node (ref "U30") (pin "128") (pinfunction "IO128_128") (pintype "bidirectional"))
    )
    (net (code "72") (name "FT5") (class "Default")
      (node (ref "U14") (pin "5") (pinfunction "D1_5") (pintype "bidirectional"))
      (node (ref "U30") (pin "127") (pinfunction "IO127_127") (pintype "bidirectional"))
    )
    (net (code "73") (name "FT6") (class "Default")
      (node (ref "U14") (pin "6") (pinfunction "D7_6") (pintype "bidirectional"))
      (node (ref "U30") (pin "126") (pinfunction "IO126_126") (pintype "bidirectional"))
    )
    (net (code "74") (name "FT9") (class "Default")
      (node (ref "U14") (pin "9") (pinfunction "D5_9") (pintype "bidirectional"))
      (node (ref "U30") (pin "125") (pinfunction "IO125_125") (pintype "bidirectional"))
    )
    (net (code "75") (name "FT10") (class "Default")
      (node (ref "U14") (pin "10") (pinfunction "D6_10") (pintype "bidirectional"))
      (node (ref "U30") (pin "124") (pinfunction "IO124_124") (pintype "bidirectional"))
    )
    (net (code "76") (name "FT11") (class "Default")
      (node (ref "U14") (pin "11") (pinfunction "D3_11") (pintype "bidirectional"))
      (node (ref "U30") (pin "119") (pinfunction "IO119_119") (pintype "bidirectional"))
    )
    (net (code "77") (name "FT13") (class "Default")
      (node (ref "U14") (pin "13") (pinfunction "RD#_13") (pintype "bidirectional"))
      (node (ref "U30") (pin "114") (pinfunction "IO114_114") (pintype "bidirectional"))
    )
    (net (code "78") (name "FT14") (class "Default")
      (node (ref "U14") (pin "14") (pinfunction "WR_14") (pintype "bidirectional"))
      (node (ref "U30") (pin "115") (pinfunction "IO115_115") (pintype "bidirectional"))
    )
    (net (code "79") (name "FT19") (class "Default")
      (node (ref "U14") (pin "19") (pinfunction "RESET#_19") (pintype "bidirectional"))
      (node (ref "U30") (pin "110") (pinfunction "IO110_110") (pintype "bidirectional"))
    )
    (net (code "80") (name "FT22") (class "Default")
      (node (ref "U14") (pin "22") (pinfunction "TXE#_22") (pintype "bidirectional"))
      (node (ref "U30") (pin "136") (pinfunction "IO136_136") (pintype "bidirectional"))
    )
    (net (code "81") (name "FT23") (class "Default")
      (node (ref "U14") (pin "23") (pinfunction "RXF#_23") (pintype "bidirectional"))
      (node (ref "U30") (pin "137") (pinfunction "IO137_137") (pintype "bidirectional"))
    )
    (net (code "82") (name "GI01") (class "Default")
      (node (ref "J04") (pin "1") (pinfunction "1_1") (pintype "passive"))
      (node (ref "U30") (pin "111") (pinfunction "IO111_111") (pintype "bidirectional"))
    )
    (net (code "83") (name "GI03") (class "Default")
      (node (ref "J04") (pin "3") (pinfunction "3_3") (pintype "passive"))
      (node (ref "U30") (pin "106") (pinfunction "IO106_106") (pintype "bidirectional"))
    )
    (net (code "84") (name "GI04") (class "Default")
      (node (ref "J04") (pin "4") (pinfunction "4_4") (pintype "passive"))
      (node (ref "R19") (pin "1") (pinfunction "1_1") (pintype "passive"))
      (node (ref "U30") (pin "105") (pinfunction "IO105_105") (pintype "bidirectional"))
    )
    (net (code "85") (name "GND") (class "Default")
      (node (ref "AS") (pin "10") (pinfunction "2_10") (pintype "passive"))
      (node (ref "AS") (pin "2") (pinfunction "2_2") (pintype "passive"))
      (node (ref "C11") (pin "2") (pinfunction "2_2") (pintype "passive"))
      (node (ref "C12") (pin "2") (pinfunction "2_2") (pintype "passive"))
      (node (ref "C13") (pin "2") (pinfunction "2_2") (pintype "passive"))
      (node (ref "C15") (pin "2") (pinfunction "2_2") (pintype "passive"))
      (node (ref "C17") (pin "2") (pinfunction "2_2") (pintype "passive"))
      (node (ref "C18") (pin "2") (pinfunction "2_2") (pintype "passive"))
      (node (ref "C19") (pin "2") (pinfunction "2_2") (pintype "passive"))
      (node (ref "C20") (pin "2") (pinfunction "2_2") (pintype "passive"))
      (node (ref "C21") (pin "2") (pinfunction "2_2") (pintype "passive"))
      (node (ref "C22") (pin "2") (pinfunction "2_2") (pintype "passive"))
      (node (ref "C25") (pin "2") (pinfunction "2_2") (pintype "passive"))
      (node (ref "C26") (pin "2") (pinfunction "2_2") (pintype "passive"))
      (node (ref "C27") (pin "2") (pinfunction "2_2") (pintype "passive"))
      (node (ref "C28") (pin "2") (pinfunction "2_2") (pintype "passive"))
      (node (ref "C29") (pin "2") (pinfunction "2_2") (pintype "passive"))
      (node (ref "C3") (pin "2") (pinfunction "2_2") (pintype "passive"))
      (node (ref "C30") (pin "2") (pinfunction "2_2") (pintype "passive"))
      (node (ref "C31") (pin "2") (pinfunction "2_2") (pintype "passive"))
      (node (ref "C32") (pin "2") (pinfunction "2_2") (pintype "passive"))
      (node (ref "C33") (pin "2") (pinfunction "2_2") (pintype "passive"))
      (node (ref "C34") (pin "2") (pinfunction "2_2") (pintype "passive"))
      (node (ref "C35") (pin "2") (pinfunction "2_2") (pintype "passive"))
      (node (ref "C36") (pin "2") (pinfunction "2_2") (pintype "passive"))
      (node (ref "C37") (pin "2") (pinfunction "2_2") (pintype "passive"))
      (node (ref "C38") (pin "2") (pinfunction "2_2") (pintype "passive"))
      (node (ref "C39") (pin "2") (pinfunction "2_2") (pintype "passive"))
      (node (ref "C4") (pin "2") (pinfunction "2_2") (pintype "passive"))
      (node (ref "C40") (pin "2") (pinfunction "2_2") (pintype "passive"))
      (node (ref "C41") (pin "2") (pinfunction "2_2") (pintype "passive"))
      (node (ref "C42") (pin "2") (pinfunction "2_2") (pintype "passive"))
      (node (ref "C43") (pin "2") (pinfunction "2_2") (pintype "passive"))
      (node (ref "C44") (pin "2") (pinfunction "2_2") (pintype "passive"))
      (node (ref "C45") (pin "2") (pinfunction "2_2") (pintype "passive"))
      (node (ref "C46") (pin "2") (pinfunction "2_2") (pintype "passive"))
      (node (ref "C47") (pin "2") (pinfunction "2_2") (pintype "passive"))
      (node (ref "C48") (pin "2") (pinfunction "2_2") (pintype "passive"))
      (node (ref "C49") (pin "2") (pinfunction "2_2") (pintype "passive"))
      (node (ref "C5") (pin "2") (pinfunction "2_2") (pintype "passive"))
      (node (ref "C50") (pin "2") (pinfunction "2_2") (pintype "passive"))
      (node (ref "C51") (pin "2") (pinfunction "2_2") (pintype "passive"))
      (node (ref "C52") (pin "2") (pinfunction "2_2") (pintype "passive"))
      (node (ref "C53") (pin "2") (pinfunction "2_2") (pintype "passive"))
      (node (ref "C54") (pin "2") (pinfunction "2_2") (pintype "passive"))
      (node (ref "C55") (pin "2") (pinfunction "2_2") (pintype "passive"))
      (node (ref "C56") (pin "2") (pinfunction "2_2") (pintype "passive"))
      (node (ref "C57") (pin "2") (pinfunction "2_2") (pintype "passive"))
      (node (ref "C58") (pin "2") (pinfunction "2_2") (pintype "passive"))
      (node (ref "C59") (pin "2") (pinfunction "2_2") (pintype "passive"))
      (node (ref "C6") (pin "2") (pinfunction "2_2") (pintype "passive"))
      (node (ref "C60") (pin "2") (pinfunction "2_2") (pintype "passive"))
      (node (ref "C61") (pin "2") (pinfunction "2_2") (pintype "passive"))
      (node (ref "C62") (pin "2") (pinfunction "2_2") (pintype "passive"))
      (node (ref "C64") (pin "2") (pinfunction "2_2") (pintype "passive"))
      (node (ref "C65") (pin "2") (pinfunction "2_2") (pintype "passive"))
      (node (ref "C66") (pin "2") (pinfunction "2_2") (pintype "passive"))
      (node (ref "C67") (pin "2") (pinfunction "2_2") (pintype "passive"))
      (node (ref "C68") (pin "2") (pinfunction "2_2") (pintype "passive"))
      (node (ref "C69") (pin "2") (pinfunction "2_2") (pintype "passive"))
      (node (ref "C70") (pin "2") (pinfunction "2_2") (pintype "passive"))
      (node (ref "C71") (pin "2") (pinfunction "2_2") (pintype "passive"))
      (node (ref "D6") (pin "C") (pinfunction "C_C") (pintype "passive"))
      (node (ref "J01") (pin "1") (pinfunction "1_1") (pintype "passive"))
      (node (ref "J02") (pin "4") (pinfunction "4_4") (pintype "input"))
      (node (ref "J02") (pin "5") (pinfunction "5_5") (pintype "input"))
      (node (ref "J04") (pin "2") (pinfunction "2_2") (pintype "passive"))
      (node (ref "J05") (pin "2") (pinfunction "2_2") (pintype "passive"))
      (node (ref "J11") (pin "G@1") (pinfunction "GND_G@1") (pintype "power_in"))
      (node (ref "J12") (pin "G@1") (pinfunction "GND_G@1") (pintype "power_in"))
      (node (ref "J13") (pin "1") (pinfunction "1_1") (pintype "passive"))
      (node (ref "J19") (pin "2") (pinfunction "2_2") (pintype "passive"))
      (node (ref "J20") (pin "2") (pinfunction "2_2") (pintype "passive"))
      (node (ref "J20") (pin "8") (pinfunction "4_8") (pintype "passive"))
      (node (ref "JTAG") (pin "10") (pinfunction "2_10") (pintype "passive"))
      (node (ref "JTAG") (pin "2") (pinfunction "2_2") (pintype "passive"))
      (node (ref "R10") (pin "2") (pinfunction "2_2") (pintype "passive"))
      (node (ref "R12") (pin "2") (pinfunction "2_2") (pintype "passive"))
      (node (ref "R13") (pin "1") (pinfunction "1_1") (pintype "passive"))
      (node (ref "R15") (pin "2") (pinfunction "2_2") (pintype "passive"))
      (node (ref "R2") (pin "2") (pinfunction "2_2") (pintype "passive"))
      (node (ref "R22") (pin "2") (pinfunction "2_2") (pintype "passive"))
      (node (ref "R24") (pin "1") (pinfunction "1_1") (pintype "passive"))
      (node (ref "R29") (pin "1") (pinfunction "1_1") (pintype "passive"))
      (node (ref "R33") (pin "2") (pinfunction "2_2") (pintype "passive"))
      (node (ref "R34") (pin "2") (pinfunction "2_2") (pintype "passive"))
      (node (ref "R35") (pin "2") (pinfunction "2_2") (pintype "passive"))
      (node (ref "R36") (pin "2") (pinfunction "2_2") (pintype "passive"))
      (node (ref "R37") (pin "2") (pinfunction "2_2") (pintype "passive"))
      (node (ref "R38") (pin "2") (pinfunction "2_2") (pintype "passive"))
      (node (ref "R40") (pin "2") (pinfunction "2_2") (pintype "passive"))
      (node (ref "R41") (pin "2") (pinfunction "2_2") (pintype "passive"))
      (node (ref "R43") (pin "2") (pinfunction "2_2") (pintype "passive"))
      (node (ref "R46") (pin "2") (pinfunction "2_2") (pintype "passive"))
      (node (ref "R9") (pin "1") (pinfunction "1_1") (pintype "passive"))
      (node (ref "U$8") (pin "P$1") (pinfunction "G_P$1") (pintype "bidirectional"))
      (node (ref "U$8") (pin "P$10") (pinfunction "G_P$10") (pintype "bidirectional"))
      (node (ref "U$8") (pin "P$11") (pinfunction "G_P$11") (pintype "bidirectional"))
      (node (ref "U$8") (pin "P$12") (pinfunction "G_P$12") (pintype "bidirectional"))
      (node (ref "U$8") (pin "P$13") (pinfunction "G_P$13") (pintype "bidirectional"))
      (node (ref "U$8") (pin "P$15") (pinfunction "G_P$15") (pintype "bidirectional"))
      (node (ref "U$8") (pin "P$16") (pinfunction "G_P$16") (pintype "bidirectional"))
      (node (ref "U$8") (pin "P$17") (pinfunction "G_P$17") (pintype "bidirectional"))
      (node (ref "U$8") (pin "P$18") (pinfunction "G_P$18") (pintype "bidirectional"))
      (node (ref "U$8") (pin "P$2") (pinfunction "G_P$2") (pintype "bidirectional"))
      (node (ref "U$8") (pin "P$20") (pinfunction "G_P$20") (pintype "bidirectional"))
      (node (ref "U$8") (pin "P$21") (pinfunction "G_P$21") (pintype "bidirectional"))
      (node (ref "U$8") (pin "P$22") (pinfunction "G_P$22") (pintype "bidirectional"))
      (node (ref "U$8") (pin "P$23") (pinfunction "G_P$23") (pintype "bidirectional"))
      (node (ref "U$8") (pin "P$24") (pinfunction "G_P$24") (pintype "bidirectional"))
      (node (ref "U$8") (pin "P$25") (pinfunction "G_P$25") (pintype "bidirectional"))
      (node (ref "U$8") (pin "P$26") (pinfunction "G_P$26") (pintype "bidirectional"))
      (node (ref "U$8") (pin "P$3") (pinfunction "G_P$3") (pintype "bidirectional"))
      (node (ref "U$8") (pin "P$4") (pinfunction "G_P$4") (pintype "bidirectional"))
      (node (ref "U$8") (pin "P$5") (pinfunction "G_P$5") (pintype "bidirectional"))
      (node (ref "U$8") (pin "P$6") (pinfunction "G_P$6") (pintype "bidirectional"))
      (node (ref "U$8") (pin "P$7") (pinfunction "G_P$7") (pintype "bidirectional"))
      (node (ref "U$8") (pin "P$8") (pinfunction "G_P$8") (pintype "bidirectional"))
      (node (ref "U$8") (pin "P$9") (pinfunction "G_P$9") (pintype "bidirectional"))
      (node (ref "U04") (pin "9") (pinfunction "GND_9") (pintype "passive"))
      (node (ref "U05") (pin "A") (pinfunction "GND1_A") (pintype "bidirectional"))
      (node (ref "U05") (pin "C") (pinfunction "GND2_C") (pintype "bidirectional"))
      (node (ref "U05") (pin "D") (pinfunction "GND3_D") (pintype "bidirectional"))
      (node (ref "U05") (pin "F") (pinfunction "GND4_F") (pintype "bidirectional"))
      (node (ref "U06") (pin "A") (pinfunction "GND1_A") (pintype "bidirectional"))
      (node (ref "U06") (pin "C") (pinfunction "GND2_C") (pintype "bidirectional"))
      (node (ref "U06") (pin "D") (pinfunction "GND3_D") (pintype "bidirectional"))
      (node (ref "U06") (pin "F") (pinfunction "GND4_F") (pintype "bidirectional"))
      (node (ref "U07") (pin "1") (pinfunction "GND1_1") (pintype "passive"))
      (node (ref "U07") (pin "4") (pinfunction "GND2_4") (pintype "passive"))
      (node (ref "U07") (pin "5") (pinfunction "GND3_5") (pintype "passive"))
      (node (ref "U07") (pin "8") (pinfunction "GND4_8") (pintype "passive"))
      (node (ref "U07") (pin "9") (pinfunction "GND5_9") (pintype "passive"))
      (node (ref "U08") (pin "P3") (pinfunction "GND1_P3") (pintype "bidirectional"))
      (node (ref "U08") (pin "P4") (pinfunction "GND2_P4") (pintype "bidirectional"))
      (node (ref "U08") (pin "P7") (pinfunction "GND3_P7") (pintype "bidirectional"))
      (node (ref "U08") (pin "P8") (pinfunction "GND4_P8") (pintype "bidirectional"))
      (node (ref "U09") (pin "1") (pinfunction "SD_1") (pintype "passive"))
      (node (ref "U1") (pin "5") (pinfunction "GND_5") (pintype "passive"))
      (node (ref "U1") (pin "6") (pinfunction "GND_6") (pintype "passive"))
      (node (ref "U1") (pin "7") (pinfunction "GND_7") (pintype "passive"))
      (node (ref "U1") (pin "8") (pinfunction "GND_8") (pintype "passive"))
      (node (ref "U10") (pin "5") (pinfunction "PWDN_5") (pintype "passive"))
      (node (ref "U10") (pin "6") (pinfunction "COMM_6") (pintype "passive"))
      (node (ref "U11") (pin "2") (pinfunction "GND1_2") (pintype "power_in"))
      (node (ref "U11") (pin "3") (pinfunction "GND2_3") (pintype "power_in"))
      (node (ref "U11") (pin "5") (pinfunction "GND3_5") (pintype "power_in"))
      (node (ref "U14") (pin "18") (pinfunction "GND_18") (pintype "bidirectional"))
      (node (ref "U14") (pin "21") (pinfunction "GND_21") (pintype "bidirectional"))
      (node (ref "U14") (pin "25") (pinfunction "AGND_25") (pintype "bidirectional"))
      (node (ref "U14") (pin "26") (pinfunction "TEST_26") (pintype "bidirectional"))
      (node (ref "U14") (pin "7") (pinfunction "GND_7") (pintype "bidirectional"))
      (node (ref "U19") (pin "P1") (pinfunction "AGND_P1") (pintype "passive"))
      (node (ref "U19") (pin "P13") (pinfunction "AGND_3_P13") (pintype "passive"))
      (node (ref "U19") (pin "P16") (pinfunction "AGND_4_P16") (pintype "passive"))
      (node (ref "U19") (pin "P28") (pinfunction "DRGND_P28") (pintype "passive"))
      (node (ref "U19") (pin "P4") (pinfunction "AGND_2_P4") (pintype "passive"))
      (node (ref "U19") (pin "P40") (pinfunction "DRGND_2_P40") (pintype "passive"))
      (node (ref "U19") (pin "P53") (pinfunction "DRGND_3_P53") (pintype "passive"))
      (node (ref "U20") (pin "2") (pinfunction "GND_2") (pintype "bidirectional"))
      (node (ref "U21") (pin "4") (pinfunction "GND_4") (pintype "bidirectional"))
      (node (ref "U22") (pin "2") (pinfunction "GND_2") (pintype "passive"))
      (node (ref "U23") (pin "3") (pinfunction "WP#_3") (pintype "bidirectional"))
      (node (ref "U23") (pin "4") (pinfunction "VSS_4") (pintype "bidirectional"))
      (node (ref "U24") (pin "2") (pinfunction "GND_2") (pintype "passive"))
      (node (ref "U30") (pin "108") (pinfunction "GND_108") (pintype "power_in"))
      (node (ref "U30") (pin "118") (pinfunction "GND_118") (pintype "power_in"))
      (node (ref "U30") (pin "123") (pinfunction "GND_123") (pintype "power_in"))
      (node (ref "U30") (pin "131") (pinfunction "GND_131") (pintype "power_in"))
      (node (ref "U30") (pin "140") (pinfunction "GND_140") (pintype "power_in"))
      (node (ref "U30") (pin "145") (pinfunction "PAD_145") (pintype "power_in"))
      (node (ref "U30") (pin "19") (pinfunction "GND_19") (pintype "power_in"))
      (node (ref "U30") (pin "25") (pinfunction "CLK3_25") (pintype "passive"))
      (node (ref "U30") (pin "27") (pinfunction "GND_27") (pintype "power_in"))
      (node (ref "U30") (pin "36") (pinfunction "GND_36") (pintype "power_in"))
      (node (ref "U30") (pin "41") (pinfunction "GND_41") (pintype "power_in"))
      (node (ref "U30") (pin "48") (pinfunction "GND_48") (pintype "power_in"))
      (node (ref "U30") (pin "57") (pinfunction "GND_57") (pintype "power_in"))
      (node (ref "U30") (pin "63") (pinfunction "GND_63") (pintype "power_in"))
      (node (ref "U30") (pin "82") (pinfunction "GND_82") (pintype "power_in"))
      (node (ref "U30") (pin "94") (pinfunction "MSEL0_94") (pintype "input"))
      (node (ref "U30") (pin "95") (pinfunction "GND_95") (pintype "power_in"))
      (node (ref "U30") (pin "97") (pinfunction "MSEL2_97") (pintype "input"))
    )
    (net (code "86") (name "IF") (class "Default")
      (node (ref "J18") (pin "1") (pinfunction "1_1") (pintype "passive"))
      (node (ref "R11") (pin "1") (pinfunction "1_1") (pintype "passive"))
      (node (ref "R7") (pin "2") (pinfunction "2_2") (pintype "passive"))
      (node (ref "U10") (pin "8") (pinfunction "VOUT_8") (pintype "passive"))
      (node (ref "U19") (pin "P15") (pinfunction "VIN+_B_P15") (pintype "passive"))
    )
    (net (code "87") (name "LED1A") (class "Default")
      (node (ref "D1") (pin "A1") (pinfunction "A1_A1") (pintype "passive"))
      (node (ref "U30") (pin "73") (pinfunction "IO73_73") (pintype "bidirectional"))
    )
    (net (code "88") (name "LED1B") (class "Default")
      (node (ref "D1") (pin "A0") (pinfunction "A0_A0") (pintype "passive"))
      (node (ref "U30") (pin "75") (pinfunction "IO75_75") (pintype "bidirectional"))
    )
    (net (code "89") (name "LED2A") (class "Default")
      (node (ref "D4") (pin "A1") (pinfunction "A1_A1") (pintype "passive"))
      (node (ref "U30") (pin "79") (pinfunction "IO79_79") (pintype "bidirectional"))
    )
    (net (code "90") (name "LED2B") (class "Default")
      (node (ref "D4") (pin "A0") (pinfunction "A0_A0") (pintype "passive"))
      (node (ref "U30") (pin "80") (pinfunction "IO80_80") (pintype "bidirectional"))
    )
    (net (code "91") (name "LED3") (class "Default")
      (node (ref "D3") (pin "A") (pinfunction "A_A") (pintype "passive"))
      (node (ref "U30") (pin "87") (pinfunction "IO87_87") (pintype "bidirectional"))
    )
    (net (code "92") (name "LED4A") (class "Default")
      (node (ref "D5") (pin "A1") (pinfunction "A1_A1") (pintype "passive"))
      (node (ref "U30") (pin "98") (pinfunction "IO98_98") (pintype "bidirectional"))
    )
    (net (code "93") (name "LED4B") (class "Default")
      (node (ref "D5") (pin "A0") (pinfunction "A0_A0") (pintype "passive"))
      (node (ref "U30") (pin "99") (pinfunction "IO99_99") (pintype "bidirectional"))
    )
    (net (code "94") (name "LED5") (class "Default")
      (node (ref "D39") (pin "A") (pinfunction "A_A") (pintype "passive"))
      (node (ref "U30") (pin "104") (pinfunction "IO104_104") (pintype "bidirectional"))
    )
    (net (code "95") (name "Net-(C1-Pad2)") (class "Default")
      (node (ref "C1") (pin "2") (pinfunction "2_2") (pintype "passive"))
      (node (ref "L1") (pin "1") (pinfunction "1_1") (pintype "passive"))
      (node (ref "R2") (pin "1") (pinfunction "1_1") (pintype "passive"))
    )
    (net (code "96") (name "Net-(C8-Pad2)") (class "Default")
      (node (ref "C8") (pin "2") (pinfunction "2_2") (pintype "passive"))
      (node (ref "J12") (pin "1") (pinfunction "1_1") (pintype "passive"))
      (node (ref "R32") (pin "1") (pinfunction "1_1") (pintype "passive"))
      (node (ref "R33") (pin "1") (pinfunction "1_1") (pintype "passive"))
    )
    (net (code "97") (name "Net-(C13-Pad1)") (class "Default")
      (node (ref "C13") (pin "1") (pinfunction "1_1") (pintype "passive"))
      (node (ref "C18") (pin "1") (pinfunction "1_1") (pintype "passive"))
      (node (ref "L6") (pin "1") (pinfunction "1_1") (pintype "passive"))
      (node (ref "R16") (pin "1") (pinfunction "1_1") (pintype "passive"))
    )
    (net (code "98") (name "Net-(D1-PadC0)") (class "Default")
      (node (ref "D1") (pin "C0") (pinfunction "C0_C0") (pintype "passive"))
      (node (ref "R37") (pin "1") (pinfunction "1_1") (pintype "passive"))
    )
    (net (code "99") (name "Net-(D1-PadC1)") (class "Default")
      (node (ref "D1") (pin "C1") (pinfunction "C1_C1") (pintype "passive"))
      (node (ref "R36") (pin "1") (pinfunction "1_1") (pintype "passive"))
    )
    (net (code "100") (name "Net-(D3-PadC)") (class "Default")
      (node (ref "D3") (pin "C") (pinfunction "C_C") (pintype "passive"))
      (node (ref "R15") (pin "1") (pinfunction "1_1") (pintype "passive"))
    )
    (net (code "101") (name "Net-(D4-PadC0)") (class "Default")
      (node (ref "D4") (pin "C0") (pinfunction "C0_C0") (pintype "passive"))
      (node (ref "R22") (pin "1") (pinfunction "1_1") (pintype "passive"))
    )
    (net (code "102") (name "Net-(D4-PadC1)") (class "Default")
      (node (ref "D4") (pin "C1") (pinfunction "C1_C1") (pintype "passive"))
      (node (ref "R12") (pin "1") (pinfunction "1_1") (pintype "passive"))
    )
    (net (code "103") (name "Net-(D5-PadC0)") (class "Default")
      (node (ref "D5") (pin "C0") (pinfunction "C0_C0") (pintype "passive"))
      (node (ref "R38") (pin "1") (pinfunction "1_1") (pintype "passive"))
    )
    (net (code "104") (name "Net-(D5-PadC1)") (class "Default")
      (node (ref "D5") (pin "C1") (pinfunction "C1_C1") (pintype "passive"))
      (node (ref "R35") (pin "1") (pinfunction "1_1") (pintype "passive"))
    )
    (net (code "105") (name "Net-(D6-PadA)") (class "Default")
      (node (ref "D6") (pin "A") (pinfunction "A_A") (pintype "passive"))
      (node (ref "R19") (pin "2") (pinfunction "2_2") (pintype "passive"))
    )
    (net (code "106") (name "Net-(D39-PadC)") (class "Default")
      (node (ref "D39") (pin "C") (pinfunction "C_C") (pintype "passive"))
      (node (ref "R34") (pin "1") (pinfunction "1_1") (pintype "passive"))
    )
    (net (code "107") (name "Net-(U1-OUT)") (class "Default")
      (node (ref "C56") (pin "1") (pinfunction "1_1") (pintype "passive"))
      (node (ref "R23") (pin "1") (pinfunction "1_1") (pintype "passive"))
      (node (ref "U1") (pin "3") (pinfunction "OUT_3") (pintype "passive"))
    )
    (net (code "108") (name "Net-(U1-SS)") (class "Default")
      (node (ref "C54") (pin "1") (pinfunction "1_1") (pintype "passive"))
      (node (ref "U1") (pin "4") (pinfunction "SS_4") (pintype "passive"))
    )
    (net (code "109") (name "Net-(U04-RFIN)") (class "Default")
      (node (ref "L5") (pin "2") (pinfunction "2_2") (pintype "passive"))
      (node (ref "R41") (pin "1") (pinfunction "1_1") (pintype "passive"))
      (node (ref "U04") (pin "2") (pinfunction "RFIN_2") (pintype "passive"))
    )
    (net (code "110") (name "Net-(U04-RFOUT)") (class "Default")
      (node (ref "C1") (pin "1") (pinfunction "1_1") (pintype "passive"))
      (node (ref "C5") (pin "1") (pinfunction "1_1") (pintype "passive"))
      (node (ref "U04") (pin "7") (pinfunction "RFOUT_7") (pintype "passive"))
    )
    (net (code "111") (name "Net-(U04-VBIAS)") (class "Default")
      (node (ref "R14") (pin "2") (pinfunction "2_2") (pintype "passive"))
      (node (ref "U04") (pin "1") (pinfunction "VBIAS_1") (pintype "passive"))
    )
    (net (code "112") (name "Net-(U04-VPOS)") (class "Default")
      (node (ref "L6") (pin "2") (pinfunction "2_2") (pintype "passive"))
      (node (ref "R14") (pin "1") (pinfunction "1_1") (pintype "passive"))
      (node (ref "U04") (pin "8") (pinfunction "VPOS_8") (pintype "power_in"))
    )
    (net (code "113") (name "Net-(U05-RFI)") (class "Default")
      (node (ref "J11") (pin "1") (pinfunction "1_1") (pintype "passive"))
      (node (ref "U05") (pin "B") (pinfunction "RFI_B") (pintype "bidirectional"))
    )
    (net (code "114") (name "Net-(U05-RFO)") (class "Default")
      (node (ref "L5") (pin "1") (pinfunction "1_1") (pintype "passive"))
      (node (ref "R40") (pin "1") (pinfunction "1_1") (pintype "passive"))
      (node (ref "U05") (pin "E") (pinfunction "RFO_E") (pintype "bidirectional"))
    )
    (net (code "115") (name "Net-(U06-RFI)") (class "Default")
      (node (ref "C2") (pin "2") (pinfunction "2_2") (pintype "passive"))
      (node (ref "R43") (pin "1") (pinfunction "1_1") (pintype "passive"))
      (node (ref "U06") (pin "B") (pinfunction "RFI_B") (pintype "bidirectional"))
    )
    (net (code "116") (name "Net-(U06-RFO)") (class "Default")
      (node (ref "C14") (pin "1") (pinfunction "1_1") (pintype "passive"))
      (node (ref "R46") (pin "1") (pinfunction "1_1") (pintype "passive"))
      (node (ref "U06") (pin "E") (pinfunction "RFO_E") (pintype "bidirectional"))
    )
    (net (code "117") (name "Net-(U07-RFIN)") (class "Default")
      (node (ref "C14") (pin "2") (pinfunction "2_2") (pintype "passive"))
      (node (ref "U07") (pin "3") (pinfunction "RFIN_3") (pintype "passive"))
    )
    (net (code "118") (name "Net-(U07-RFOUT)") (class "Default")
      (node (ref "C7") (pin "1") (pinfunction "1_1") (pintype "passive"))
      (node (ref "C8") (pin "1") (pinfunction "1_1") (pintype "passive"))
      (node (ref "L2") (pin "2") (pinfunction "2_2") (pintype "passive"))
      (node (ref "U07") (pin "7") (pinfunction "RFOUT_7") (pintype "passive"))
    )
    (net (code "119") (name "Net-(U07-VPOS)") (class "Default")
      (node (ref "C17") (pin "1") (pinfunction "1_1") (pintype "passive"))
      (node (ref "C20") (pin "1") (pinfunction "1_1") (pintype "passive"))
      (node (ref "L2") (pin "1") (pinfunction "1_1") (pintype "passive"))
      (node (ref "R3") (pin "2") (pinfunction "2_2") (pintype "passive"))
      (node (ref "U07") (pin "6") (pinfunction "VPOS_6") (pintype "power_in"))
    )
    (net (code "120") (name "Net-(U08-RFIN)") (class "Default")
      (node (ref "U08") (pin "P2") (pinfunction "RFIN_P2") (pintype "bidirectional"))
      (node (ref "U09") (pin "6") (pinfunction "PD_6") (pintype "passive"))
    )
    (net (code "121") (name "Net-(U08-RFIP)") (class "Default")
      (node (ref "U08") (pin "P1") (pinfunction "RFIP_P1") (pintype "bidirectional"))
      (node (ref "U09") (pin "4") (pinfunction "P_4") (pintype "passive"))
    )
    (net (code "122") (name "Net-(U08-RFON)") (class "Default")
      (node (ref "C9") (pin "1") (pinfunction "1_1") (pintype "passive"))
      (node (ref "U08") (pin "P6") (pinfunction "RFON_P6") (pintype "bidirectional"))
    )
    (net (code "123") (name "Net-(U08-RFOP)") (class "Default")
      (node (ref "C10") (pin "1") (pinfunction "1_1") (pintype "passive"))
      (node (ref "U08") (pin "P5") (pinfunction "RFOP_P5") (pintype "bidirectional"))
    )
    (net (code "124") (name "Net-(U09-S)") (class "Default")
      (node (ref "C7") (pin "2") (pinfunction "2_2") (pintype "passive"))
      (node (ref "R32") (pin "2") (pinfunction "2_2") (pintype "passive"))
      (node (ref "U09") (pin "3") (pinfunction "S_3") (pintype "passive"))
    )
    (net (code "125") (name "Net-(U10-INHI)") (class "Default")
      (node (ref "C9") (pin "2") (pinfunction "2_2") (pintype "passive"))
      (node (ref "R8") (pin "2") (pinfunction "2_2") (pintype "passive"))
      (node (ref "U10") (pin "2") (pinfunction "INHI_2") (pintype "passive"))
    )
    (net (code "126") (name "Net-(U10-INLO)") (class "Default")
      (node (ref "C10") (pin "2") (pinfunction "2_2") (pintype "passive"))
      (node (ref "R8") (pin "1") (pinfunction "1_1") (pintype "passive"))
      (node (ref "U10") (pin "3") (pinfunction "INLO_3") (pintype "passive"))
    )
    (net (code "127") (name "Net-(U10-VPOS1)") (class "Default")
      (node (ref "C11") (pin "1") (pinfunction "1_1") (pintype "passive"))
      (node (ref "C65") (pin "1") (pinfunction "1_1") (pintype "passive"))
      (node (ref "R5") (pin "2") (pinfunction "2_2") (pintype "passive"))
      (node (ref "U10") (pin "1") (pinfunction "VPOS1_1") (pintype "power_in"))
    )
    (net (code "128") (name "Net-(U10-VPOS2)") (class "Default")
      (node (ref "C12") (pin "1") (pinfunction "1_1") (pintype "passive"))
      (node (ref "C66") (pin "1") (pinfunction "1_1") (pintype "passive"))
      (node (ref "R6") (pin "2") (pinfunction "2_2") (pintype "passive"))
      (node (ref "U10") (pin "4") (pinfunction "VPOS2_4") (pintype "passive"))
    )
    (net (code "129") (name "Net-(U10-VSET)") (class "Default")
      (node (ref "R7") (pin "1") (pinfunction "1_1") (pintype "passive"))
      (node (ref "U10") (pin "7") (pinfunction "VSET_7") (pintype "passive"))
    )
    (net (code "130") (name "Net-(U11-RFI)") (class "Default")
      (node (ref "L1") (pin "2") (pinfunction "2_2") (pintype "passive"))
      (node (ref "U11") (pin "1") (pinfunction "RFI_1") (pintype "input"))
    )
    (net (code "131") (name "Net-(U11-RFO)") (class "Default")
      (node (ref "C2") (pin "1") (pinfunction "1_1") (pintype "passive"))
      (node (ref "R10") (pin "1") (pinfunction "1_1") (pintype "passive"))
      (node (ref "U11") (pin "4") (pinfunction "RFO_4") (pintype "output"))
    )
    (net (code "132") (name "Net-(U11-VCC)") (class "Default")
      (node (ref "C19") (pin "1") (pinfunction "1_1") (pintype "passive"))
      (node (ref "C4") (pin "1") (pinfunction "1_1") (pintype "passive"))
      (node (ref "R1") (pin "2") (pinfunction "2_2") (pintype "passive"))
      (node (ref "U11") (pin "6") (pinfunction "VCC_6") (pintype "power_in"))
    )
    (net (code "133") (name "Net-(U14-3V3OUT)") (class "Default")
      (node (ref "C53") (pin "1") (pinfunction "1_1") (pintype "passive"))
      (node (ref "U14") (pin "17") (pinfunction "3V3OUT_17") (pintype "bidirectional"))
    )
    (net (code "134") (name "Net-(U14-PWREN#)") (class "Default")
      (node (ref "R17") (pin "2") (pinfunction "2_2") (pintype "passive"))
      (node (ref "U14") (pin "12") (pinfunction "PWREN#_12") (pintype "bidirectional"))
    )
    (net (code "135") (name "Net-(U14-USBDM)") (class "Default")
      (node (ref "J02") (pin "2") (pinfunction "2_2") (pintype "input"))
      (node (ref "U14") (pin "16") (pinfunction "USBDM_16") (pintype "bidirectional"))
    )
    (net (code "136") (name "Net-(U14-USBDP)") (class "Default")
      (node (ref "J02") (pin "3") (pinfunction "3_3") (pintype "input"))
      (node (ref "U14") (pin "15") (pinfunction "USBDP_15") (pintype "bidirectional"))
    )
    (net (code "137") (name "Net-(U19-REFB_A)") (class "Default")
      (node (ref "C22") (pin "1") (pinfunction "1_1") (pintype "passive"))
      (node (ref "C23") (pin "2") (pinfunction "2_2") (pintype "passive"))
      (node (ref "C24") (pin "2") (pinfunction "2_2") (pintype "passive"))
      (node (ref "U19") (pin "P10") (pinfunction "REFB_B_P10") (pintype "passive"))
      (node (ref "U19") (pin "P7") (pinfunction "REFB_A_P7") (pintype "passive"))
    )
    (net (code "138") (name "Net-(U19-REFT_A)") (class "Default")
      (node (ref "C21") (pin "1") (pinfunction "1_1") (pintype "passive"))
      (node (ref "C23") (pin "1") (pinfunction "1_1") (pintype "passive"))
      (node (ref "C24") (pin "1") (pinfunction "1_1") (pintype "passive"))
      (node (ref "U19") (pin "P11") (pinfunction "REFT_B_P11") (pintype "passive"))
      (node (ref "U19") (pin "P6") (pinfunction "REFT_A_P6") (pintype "passive"))
    )
    (net (code "139") (name "Net-(U19-SENSE)") (class "Default")
      (node (ref "R4") (pin "1") (pinfunction "1_1") (pintype "passive"))
      (node (ref "R9") (pin "2") (pinfunction "2_2") (pintype "passive"))
      (node (ref "U19") (pin "P9") (pinfunction "SENSE_P9") (pintype "passive"))
    )
    (net (code "140") (name "Net-(U19-VIN+_A)") (class "Default")
      (node (ref "J03") (pin "2") (pinfunction "2_2") (pintype "passive"))
      (node (ref "U19") (pin "P2") (pinfunction "VIN+_A_P2") (pintype "passive"))
    )
    (net (code "141") (name "Net-(U19-VIN-_A)") (class "Default")
      (node (ref "J03") (pin "1") (pinfunction "1_1") (pintype "passive"))
      (node (ref "U19") (pin "P3") (pinfunction "VIN-_A_P3") (pintype "passive"))
    )
    (net (code "142") (name "Net-(U19-VIN-_B)") (class "Default")
      (node (ref "R13") (pin "2") (pinfunction "2_2") (pintype "passive"))
      (node (ref "R20") (pin "1") (pinfunction "1_1") (pintype "passive"))
      (node (ref "U19") (pin "P14") (pinfunction "VIN-_B_P14") (pintype "passive"))
    )
    (net (code "143") (name "Net-(U19-VREF)") (class "Default")
      (node (ref "C25") (pin "1") (pinfunction "1_1") (pintype "passive"))
      (node (ref "C26") (pin "1") (pinfunction "1_1") (pintype "passive"))
      (node (ref "R4") (pin "2") (pinfunction "2_2") (pintype "passive"))
      (node (ref "U19") (pin "P8") (pinfunction "VREF_P8") (pintype "passive"))
    )
    (net (code "144") (name "Net-(U22-VOUT)") (class "Default")
      (node (ref "C60") (pin "1") (pinfunction "1_1") (pintype "passive"))
      (node (ref "R21") (pin "1") (pinfunction "1_1") (pintype "passive"))
      (node (ref "U22") (pin "5") (pinfunction "VOUT_5") (pintype "passive"))
    )
    (net (code "145") (name "Net-(U24-VOUT)") (class "Default")
      (node (ref "C59") (pin "1") (pinfunction "1_1") (pintype "passive"))
      (node (ref "R18") (pin "1") (pinfunction "1_1") (pintype "passive"))
      (node (ref "U24") (pin "5") (pinfunction "VOUT_5") (pintype "passive"))
    )
    (net (code "146") (name "Net-(U30-NSTATUS)") (class "Default")
      (node (ref "R27") (pin "1") (pinfunction "1_1") (pintype "passive"))
      (node (ref "U30") (pin "9") (pinfunction "NSTATUS_9") (pintype "input"))
    )
    (net (code "147") (name "SST1") (class "Default")
      (node (ref "U23") (pin "1") (pinfunction "CE#_1") (pintype "bidirectional"))
      (node (ref "U30") (pin "74") (pinfunction "IO74_74") (pintype "bidirectional"))
    )
    (net (code "148") (name "SST2") (class "Default")
      (node (ref "U23") (pin "2") (pinfunction "SO_2") (pintype "bidirectional"))
      (node (ref "U30") (pin "69") (pinfunction "IO69_69") (pintype "bidirectional"))
    )
    (net (code "149") (name "SST5") (class "Default")
      (node (ref "U23") (pin "5") (pinfunction "SI_5") (pintype "bidirectional"))
      (node (ref "U30") (pin "67") (pinfunction "IO67_67") (pintype "bidirectional"))
    )
    (net (code "150") (name "SST6") (class "Default")
      (node (ref "U23") (pin "6") (pinfunction "SCK_6") (pintype "bidirectional"))
      (node (ref "U30") (pin "68") (pinfunction "IO68_68") (pintype "bidirectional"))
    )
    (net (code "151") (name "SST7") (class "Default")
      (node (ref "U23") (pin "7") (pinfunction "HOLD#_7") (pintype "bidirectional"))
      (node (ref "U30") (pin "76") (pinfunction "IO76_76") (pintype "bidirectional"))
    )
    (net (code "152") (name "USB5V") (class "Default")
      (node (ref "C55") (pin "1") (pinfunction "1_1") (pintype "passive"))
      (node (ref "C6") (pin "1") (pinfunction "1_1") (pintype "passive"))
      (node (ref "J02") (pin "1") (pinfunction "1_1") (pintype "input"))
      (node (ref "R31") (pin "1") (pinfunction "1_1") (pintype "passive"))
    )
    (net (code "153") (name "VDD") (class "Default")
      (node (ref "C37") (pin "1") (pinfunction "1_1") (pintype "passive"))
      (node (ref "C38") (pin "1") (pinfunction "1_1") (pintype "passive"))
      (node (ref "C39") (pin "1") (pinfunction "1_1") (pintype "passive"))
      (node (ref "C40") (pin "1") (pinfunction "1_1") (pintype "passive"))
      (node (ref "C41") (pin "1") (pinfunction "1_1") (pintype "passive"))
      (node (ref "C42") (pin "1") (pinfunction "1_1") (pintype "passive"))
      (node (ref "C43") (pin "1") (pinfunction "1_1") (pintype "passive"))
      (node (ref "C44") (pin "1") (pinfunction "1_1") (pintype "passive"))
      (node (ref "C45") (pin "1") (pinfunction "1_1") (pintype "passive"))
      (node (ref "C46") (pin "1") (pinfunction "1_1") (pintype "passive"))
      (node (ref "C64") (pin "1") (pinfunction "1_1") (pintype "passive"))
      (node (ref "R21") (pin "2") (pinfunction "2_2") (pintype "passive"))
      (node (ref "U30") (pin "102") (pinfunction "VCCINT_102") (pintype "power_in"))
      (node (ref "U30") (pin "109") (pinfunction "VCCD_109") (pintype "power_in"))
      (node (ref "U30") (pin "116") (pinfunction "VCCINT_116") (pintype "power_in"))
      (node (ref "U30") (pin "134") (pinfunction "VCCINT_134") (pintype "power_in"))
      (node (ref "U30") (pin "29") (pinfunction "VCCINT_29") (pintype "power_in"))
      (node (ref "U30") (pin "37") (pinfunction "VCCD_37") (pintype "power_in"))
      (node (ref "U30") (pin "45") (pinfunction "VCCINT_45") (pintype "power_in"))
      (node (ref "U30") (pin "5") (pinfunction "VCCINT_5") (pintype "power_in"))
      (node (ref "U30") (pin "61") (pinfunction "VCCINT_61") (pintype "power_in"))
      (node (ref "U30") (pin "78") (pinfunction "VCCINT_78") (pintype "power_in"))
    )
    (net (code "154") (name "VPP") (class "Default")
      (node (ref "C47") (pin "1") (pinfunction "1_1") (pintype "passive"))
      (node (ref "C48") (pin "1") (pinfunction "1_1") (pintype "passive"))
      (node (ref "C49") (pin "1") (pinfunction "1_1") (pintype "passive"))
      (node (ref "C50") (pin "1") (pinfunction "1_1") (pintype "passive"))
      (node (ref "C51") (pin "1") (pinfunction "1_1") (pintype "passive"))
      (node (ref "C52") (pin "1") (pinfunction "1_1") (pintype "passive"))
      (node (ref "JTAG") (pin "4") (pinfunction "2_4") (pintype "passive"))
      (node (ref "R18") (pin "2") (pinfunction "2_2") (pintype "passive"))
      (node (ref "R25") (pin "2") (pinfunction "2_2") (pintype "passive"))
      (node (ref "R26") (pin "2") (pinfunction "2_2") (pintype "passive"))
      (node (ref "U30") (pin "107") (pinfunction "VCCA_107") (pintype "power_in"))
      (node (ref "U30") (pin "35") (pinfunction "VCCA_35") (pintype "power_in"))
      (node (ref "U30") (pin "96") (pinfunction "MSEL1_96") (pintype "input"))
    )
    (net (code "155") (name "XO") (class "Default")
      (node (ref "U20") (pin "3") (pinfunction "OUT_3") (pintype "bidirectional"))
      (node (ref "U30") (pin "22") (pinfunction "CLK0_22") (pintype "passive"))
    )
    (net (code "156") (name "unconnected-(JTAGC-2-Pad6)") (class "Default")
      (node (ref "JTAG") (pin "6") (pinfunction "2_6") (pintype "passive"))
    )
    (net (code "157") (name "unconnected-(JTAGD-1-Pad7)") (class "Default")
      (node (ref "JTAG") (pin "7") (pinfunction "1_7") (pintype "passive"))
    )
    (net (code "158") (name "unconnected-(JTAGD-2-Pad8)") (class "Default")
      (node (ref "JTAG") (pin "8") (pinfunction "2_8") (pintype "passive"))
    )
    (net (code "159") (name "unconnected-(U04-NC1-Pad3)") (class "Default")
      (node (ref "U04") (pin "3") (pinfunction "NC1_3") (pintype "passive"))
    )
    (net (code "160") (name "unconnected-(U04-NC2-Pad4)") (class "Default")
      (node (ref "U04") (pin "4") (pinfunction "NC2_4") (pintype "passive"))
    )
    (net (code "161") (name "unconnected-(U04-NC3-Pad5)") (class "Default")
      (node (ref "U04") (pin "5") (pinfunction "NC3_5") (pintype "passive"))
    )
    (net (code "162") (name "unconnected-(U04-NC4-Pad6)") (class "Default")
      (node (ref "U04") (pin "6") (pinfunction "NC4_6") (pintype "passive"))
    )
    (net (code "163") (name "unconnected-(U07-NC-Pad2)") (class "Default")
      (node (ref "U07") (pin "2") (pinfunction "NC_2") (pintype "passive"))
    )
    (net (code "164") (name "unconnected-(U14-NC1-Pad8)") (class "Default")
      (node (ref "U14") (pin "8") (pinfunction "NC1_8") (pintype "bidirectional"))
    )
    (net (code "165") (name "unconnected-(U14-NC2-Pad24)") (class "Default")
      (node (ref "U14") (pin "24") (pinfunction "NC2_24") (pintype "bidirectional"))
    )
    (net (code "166") (name "unconnected-(U14-OSCI-Pad27)") (class "Default")
      (node (ref "U14") (pin "27") (pinfunction "OSCI_27") (pintype "bidirectional"))
    )
    (net (code "167") (name "unconnected-(U14-OSCO-Pad28)") (class "Default")
      (node (ref "U14") (pin "28") (pinfunction "OSCO_28") (pintype "bidirectional"))
    )
    (net (code "168") (name "unconnected-(U19-DNC-PadP23)") (class "Default")
      (node (ref "U19") (pin "P23") (pinfunction "DNC_P23") (pintype "passive"))
    )
    (net (code "169") (name "unconnected-(U19-DNC_2-PadP24)") (class "Default")
      (node (ref "U19") (pin "P24") (pinfunction "DNC_2_P24") (pintype "passive"))
    )
    (net (code "170") (name "unconnected-(U19-DNC_3-PadP42)") (class "Default")
      (node (ref "U19") (pin "P42") (pinfunction "DNC_3_P42") (pintype "passive"))
    )
    (net (code "171") (name "unconnected-(U19-DNC_4-PadP43)") (class "Default")
      (node (ref "U19") (pin "P43") (pinfunction "DNC_4_P43") (pintype "passive"))
    )
    (net (code "172") (name "unconnected-(U22-NC-Pad4)") (class "Default")
      (node (ref "U22") (pin "4") (pinfunction "NC_4") (pintype "passive"))
    )
    (net (code "173") (name "unconnected-(U24-NC-Pad4)") (class "Default")
      (node (ref "U24") (pin "4") (pinfunction "NC_4") (pintype "passive"))
    )
    (net (code "174") (name "unconnected-(U30-IO28-Pad28)") (class "Default")
      (node (ref "U30") (pin "28") (pinfunction "IO28_28") (pintype "bidirectional"))
    )
    (net (code "175") (name "unconnected-(U30-IO120-Pad120)") (class "Default")
      (node (ref "U30") (pin "120") (pinfunction "IO120_120") (pintype "bidirectional"))
    )
    (net (code "176") (name "unconnected-(U30-IO121-Pad121)") (class "Default")
      (node (ref "U30") (pin "121") (pinfunction "IO121_121") (pintype "bidirectional"))
    )
    (net (code "177") (name "unconnected-(U30-IO132-Pad132)") (class "Default")
      (node (ref "U30") (pin "132") (pinfunction "IO132_132") (pintype "bidirectional"))
    )
    (net (code "178") (name "unconnected-(U30-IO133-Pad133)") (class "Default")
      (node (ref "U30") (pin "133") (pinfunction "IO133_133") (pintype "bidirectional"))
    )
  )
)
